# 11_FPGA_power.net
KiCad netlist of a schematic drawn in Altium Designer
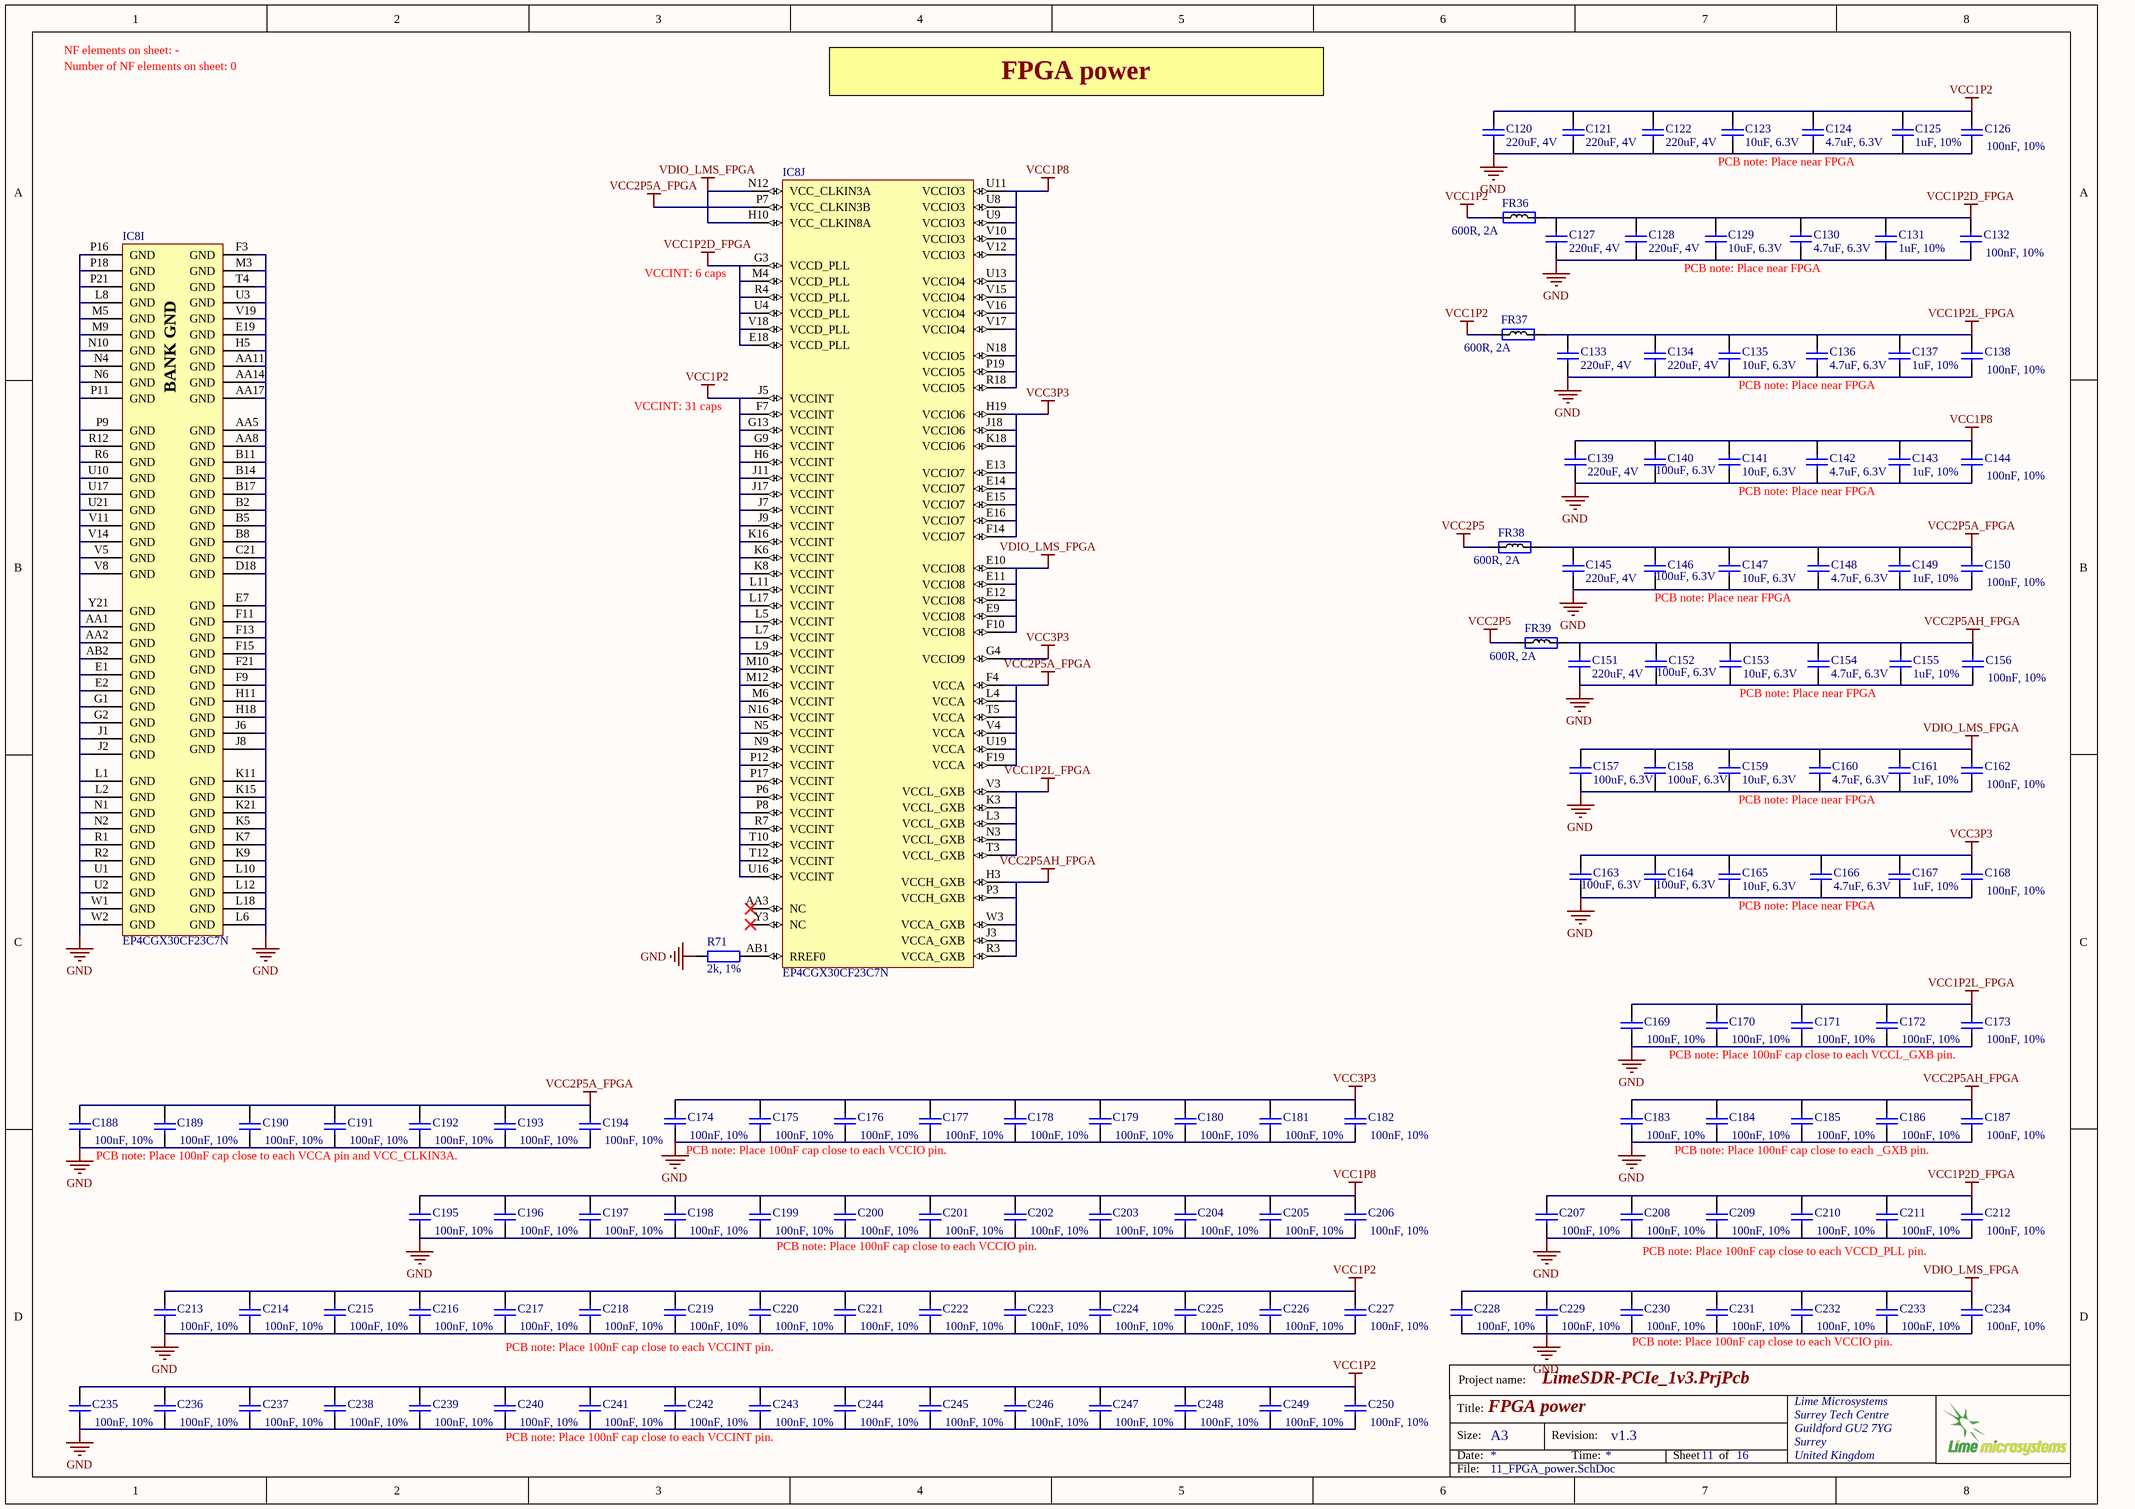
[diagram p0: 11_FPGA_power.SchDoc]

(export (version "E")
  (design (tool "Eeschema 10.0.6"))
  (components
    (comp (ref "C120")
      (value "220uF, 4V")
      (footprint "CAP1206")
      (fields
        (field (name "MANUFACTURER PART NUMBER") "GRM31CR60G227ME11L")
        (field (name "MANUFACTURER") "Murata Electronics North America")
        (field (name "TOLERANCE") "±20%")
      )
      (libsource (lib "LimeFPGAboard_schLib") (part "Cap_1206"))
    )
    (comp (ref "C121")
      (value "220uF, 4V")
      (footprint "CAP1206")
      (fields
        (field (name "MANUFACTURER PART NUMBER") "GRM31CR60G227ME11L")
        (field (name "MANUFACTURER") "Murata Electronics North America")
        (field (name "TOLERANCE") "±20%")
      )
      (libsource (lib "LimeFPGAboard_schLib") (part "Cap_1206"))
    )
    (comp (ref "C122")
      (value "220uF, 4V")
      (footprint "CAP1206")
      (fields
        (field (name "MANUFACTURER PART NUMBER") "GRM31CR60G227ME11L")
        (field (name "MANUFACTURER") "Murata Electronics North America")
        (field (name "TOLERANCE") "±20%")
      )
      (libsource (lib "LimeFPGAboard_schLib") (part "Cap_1206"))
    )
    (comp (ref "C123")
      (value "10uF, 6.3V")
      (footprint "CAP0603")
      (fields (field (name "TOLERANCE") "±20%") (field (name "MANUFACTURER") "Yageo"))
      (libsource (lib "LimeFPGAboard_schLib") (part "Cap_0603"))
    )
    (comp (ref "C124")
      (value "4.7uF, 6.3V")
      (footprint "CAP0402")
      (fields
        (field (name "MANUFACTURER") "Murata Electronics North America")
        (field (name "TOLERANCE") "±20%")
      )
      (libsource (lib "LimeMicroAltiumLib_schLib") (part "Cap_0402"))
    )
    (comp (ref "C125")
      (value "1uF, 10%")
      (footprint "CAP0402")
      (fields (field (name "MANUFACTURER") "TDK"))
      (libsource (lib "LimeMicroAltiumLib_schLib") (part "Cap_0402"))
    )
    (comp (ref "C126")
      (value "100nF, 10%")
      (footprint "CAP0402")
      (fields
        (field (name "TOLERANCE") "10 %")
        (field (name "MANUFACTURER") "Murata Electronics")
        (field (name "MANUFACTURER PART NUMBER") "GRM155R71C104KA88D")
      )
      (libsource (lib "LimeFPGAboard_schLib") (part "Cap_0603"))
    )
    (comp (ref "C127")
      (value "220uF, 4V")
      (footprint "CAP1206")
      (fields
        (field (name "MANUFACTURER PART NUMBER") "GRM31CR60G227ME11L")
        (field (name "MANUFACTURER") "Murata Electronics North America")
        (field (name "TOLERANCE") "±20%")
      )
      (libsource (lib "LimeFPGAboard_schLib") (part "Cap_1206"))
    )
    (comp (ref "C128")
      (value "220uF, 4V")
      (footprint "CAP1206")
      (fields
        (field (name "MANUFACTURER PART NUMBER") "GRM31CR60G227ME11L")
        (field (name "MANUFACTURER") "Murata Electronics North America")
        (field (name "TOLERANCE") "±20%")
      )
      (libsource (lib "LimeFPGAboard_schLib") (part "Cap_1206"))
    )
    (comp (ref "C129")
      (value "10uF, 6.3V")
      (footprint "CAP0603")
      (fields (field (name "TOLERANCE") "±20%") (field (name "MANUFACTURER") "Yageo"))
      (libsource (lib "LimeFPGAboard_schLib") (part "Cap_0603"))
    )
    (comp (ref "C130")
      (value "4.7uF, 6.3V")
      (footprint "CAP0402")
      (fields
        (field (name "MANUFACTURER") "Murata Electronics North America")
        (field (name "TOLERANCE") "±20%")
      )
      (libsource (lib "LimeMicroAltiumLib_schLib") (part "Cap_0402"))
    )
    (comp (ref "C131")
      (value "1uF, 10%")
      (footprint "CAP0402")
      (fields (field (name "MANUFACTURER") "TDK"))
      (libsource (lib "LimeMicroAltiumLib_schLib") (part "Cap_0402"))
    )
    (comp (ref "C132")
      (value "100nF, 10%")
      (footprint "CAP0402")
      (fields
        (field (name "TOLERANCE") "10 %")
        (field (name "MANUFACTURER") "Murata Electronics")
        (field (name "MANUFACTURER PART NUMBER") "GRM155R71C104KA88D")
      )
      (libsource (lib "LimeFPGAboard_schLib") (part "Cap_0603"))
    )
    (comp (ref "C133")
      (value "220uF, 4V")
      (footprint "CAP1206")
      (fields
        (field (name "MANUFACTURER PART NUMBER") "GRM31CR60G227ME11L")
        (field (name "MANUFACTURER") "Murata Electronics North America")
        (field (name "TOLERANCE") "±20%")
      )
      (libsource (lib "LimeFPGAboard_schLib") (part "Cap_1206"))
    )
    (comp (ref "C134")
      (value "220uF, 4V")
      (footprint "CAP1206")
      (fields
        (field (name "MANUFACTURER PART NUMBER") "GRM31CR60G227ME11L")
        (field (name "MANUFACTURER") "Murata Electronics North America")
        (field (name "TOLERANCE") "±20%")
      )
      (libsource (lib "LimeFPGAboard_schLib") (part "Cap_1206"))
    )
    (comp (ref "C135")
      (value "10uF, 6.3V")
      (footprint "CAP0603")
      (fields (field (name "TOLERANCE") "±20%") (field (name "MANUFACTURER") "Yageo"))
      (libsource (lib "LimeFPGAboard_schLib") (part "Cap_0603"))
    )
    (comp (ref "C136")
      (value "4.7uF, 6.3V")
      (footprint "CAP0402")
      (fields
        (field (name "MANUFACTURER") "Murata Electronics North America")
        (field (name "TOLERANCE") "±20%")
      )
      (libsource (lib "LimeMicroAltiumLib_schLib") (part "Cap_0402"))
    )
    (comp (ref "C137")
      (value "1uF, 10%")
      (footprint "CAP0402")
      (fields (field (name "MANUFACTURER") "TDK"))
      (libsource (lib "LimeMicroAltiumLib_schLib") (part "Cap_0402"))
    )
    (comp (ref "C138")
      (value "100nF, 10%")
      (footprint "CAP0402")
      (fields
        (field (name "TOLERANCE") "10 %")
        (field (name "MANUFACTURER") "Murata Electronics")
        (field (name "MANUFACTURER PART NUMBER") "GRM155R71C104KA88D")
      )
      (libsource (lib "LimeFPGAboard_schLib") (part "Cap_0603"))
    )
    (comp (ref "C139")
      (value "220uF, 4V")
      (footprint "CAP1206")
      (fields
        (field (name "MANUFACTURER PART NUMBER") "GRM31CR60G227ME11L")
        (field (name "MANUFACTURER") "Murata Electronics North America")
        (field (name "TOLERANCE") "±20%")
      )
      (libsource (lib "LimeFPGAboard_schLib") (part "Cap_1206"))
    )
    (comp (ref "C140")
      (value "100uF, 6.3V")
      (footprint "CAP1206")
      (fields (field (name "MANUFACTURER") "MURATA"))
      (libsource (lib "LimeFPGAboard_schLib") (part "Cap_1206"))
    )
    (comp (ref "C141")
      (value "10uF, 6.3V")
      (footprint "CAP0603")
      (fields (field (name "TOLERANCE") "±20%") (field (name "MANUFACTURER") "Yageo"))
      (libsource (lib "LimeFPGAboard_schLib") (part "Cap_0603"))
    )
    (comp (ref "C142")
      (value "4.7uF, 6.3V")
      (footprint "CAP0402")
      (fields
        (field (name "MANUFACTURER") "Murata Electronics North America")
        (field (name "TOLERANCE") "±20%")
      )
      (libsource (lib "LimeMicroAltiumLib_schLib") (part "Cap_0402"))
    )
    (comp (ref "C143")
      (value "1uF, 10%")
      (footprint "CAP0402")
      (fields (field (name "MANUFACTURER") "TDK"))
      (libsource (lib "LimeMicroAltiumLib_schLib") (part "Cap_0402"))
    )
    (comp (ref "C144")
      (value "100nF, 10%")
      (footprint "CAP0402")
      (fields
        (field (name "TOLERANCE") "10 %")
        (field (name "MANUFACTURER") "Murata Electronics")
        (field (name "MANUFACTURER PART NUMBER") "GRM155R71C104KA88D")
      )
      (libsource (lib "LimeFPGAboard_schLib") (part "Cap_0603"))
    )
    (comp (ref "C145")
      (value "220uF, 4V")
      (footprint "CAP1206")
      (fields
        (field (name "MANUFACTURER PART NUMBER") "GRM31CR60G227ME11L")
        (field (name "MANUFACTURER") "Murata Electronics North America")
        (field (name "TOLERANCE") "±20%")
      )
      (libsource (lib "LimeFPGAboard_schLib") (part "Cap_1206"))
    )
    (comp (ref "C146")
      (value "100uF, 6.3V")
      (footprint "CAP1206")
      (fields (field (name "MANUFACTURER") "MURATA"))
      (libsource (lib "LimeFPGAboard_schLib") (part "Cap_1206"))
    )
    (comp (ref "C147")
      (value "10uF, 6.3V")
      (footprint "CAP0603")
      (fields (field (name "TOLERANCE") "±20%") (field (name "MANUFACTURER") "Yageo"))
      (libsource (lib "LimeFPGAboard_schLib") (part "Cap_0603"))
    )
    (comp (ref "C148")
      (value "4.7uF, 6.3V")
      (footprint "CAP0402")
      (fields
        (field (name "MANUFACTURER") "Murata Electronics North America")
        (field (name "TOLERANCE") "±20%")
      )
      (libsource (lib "LimeMicroAltiumLib_schLib") (part "Cap_0402"))
    )
    (comp (ref "C149")
      (value "1uF, 10%")
      (footprint "CAP0402")
      (fields (field (name "MANUFACTURER") "TDK"))
      (libsource (lib "LimeMicroAltiumLib_schLib") (part "Cap_0402"))
    )
    (comp (ref "C150")
      (value "100nF, 10%")
      (footprint "CAP0402")
      (fields
        (field (name "TOLERANCE") "10 %")
        (field (name "MANUFACTURER") "Murata Electronics")
        (field (name "MANUFACTURER PART NUMBER") "GRM155R71C104KA88D")
      )
      (libsource (lib "LimeFPGAboard_schLib") (part "Cap_0603"))
    )
    (comp (ref "C151")
      (value "220uF, 4V")
      (footprint "CAP1206")
      (fields
        (field (name "MANUFACTURER PART NUMBER") "GRM31CR60G227ME11L")
        (field (name "MANUFACTURER") "Murata Electronics North America")
        (field (name "TOLERANCE") "±20%")
      )
      (libsource (lib "LimeFPGAboard_schLib") (part "Cap_1206"))
    )
    (comp (ref "C152")
      (value "100uF, 6.3V")
      (footprint "CAP1206")
      (fields (field (name "MANUFACTURER") "MURATA"))
      (libsource (lib "LimeFPGAboard_schLib") (part "Cap_1206"))
    )
    (comp (ref "C153")
      (value "10uF, 6.3V")
      (footprint "CAP0603")
      (fields (field (name "TOLERANCE") "±20%") (field (name "MANUFACTURER") "Yageo"))
      (libsource (lib "LimeFPGAboard_schLib") (part "Cap_0603"))
    )
    (comp (ref "C154")
      (value "4.7uF, 6.3V")
      (footprint "CAP0402")
      (fields
        (field (name "MANUFACTURER") "Murata Electronics North America")
        (field (name "TOLERANCE") "±20%")
      )
      (libsource (lib "LimeMicroAltiumLib_schLib") (part "Cap_0402"))
    )
    (comp (ref "C155")
      (value "1uF, 10%")
      (footprint "CAP0402")
      (fields (field (name "MANUFACTURER") "TDK"))
      (libsource (lib "LimeMicroAltiumLib_schLib") (part "Cap_0402"))
    )
    (comp (ref "C156")
      (value "100nF, 10%")
      (footprint "CAP0402")
      (fields
        (field (name "TOLERANCE") "10 %")
        (field (name "MANUFACTURER") "Murata Electronics")
        (field (name "MANUFACTURER PART NUMBER") "GRM155R71C104KA88D")
      )
      (libsource (lib "LimeFPGAboard_schLib") (part "Cap_0603"))
    )
    (comp (ref "C157")
      (value "100uF, 6.3V")
      (footprint "CAP1206")
      (fields (field (name "MANUFACTURER") "MURATA"))
      (libsource (lib "LimeFPGAboard_schLib") (part "Cap_1206"))
    )
    (comp (ref "C158")
      (value "100uF, 6.3V")
      (footprint "CAP1206")
      (fields (field (name "MANUFACTURER") "MURATA"))
      (libsource (lib "LimeFPGAboard_schLib") (part "Cap_1206"))
    )
    (comp (ref "C159")
      (value "10uF, 6.3V")
      (footprint "CAP0603")
      (fields (field (name "TOLERANCE") "±20%") (field (name "MANUFACTURER") "Yageo"))
      (libsource (lib "LimeFPGAboard_schLib") (part "Cap_0603"))
    )
    (comp (ref "C160")
      (value "4.7uF, 6.3V")
      (footprint "CAP0402")
      (fields
        (field (name "MANUFACTURER") "Murata Electronics North America")
        (field (name "TOLERANCE") "±20%")
      )
      (libsource (lib "LimeMicroAltiumLib_schLib") (part "Cap_0402"))
    )
    (comp (ref "C161")
      (value "1uF, 10%")
      (footprint "CAP0402")
      (fields (field (name "MANUFACTURER") "TDK"))
      (libsource (lib "LimeMicroAltiumLib_schLib") (part "Cap_0402"))
    )
    (comp (ref "C162")
      (value "100nF, 10%")
      (footprint "CAP0402")
      (fields
        (field (name "TOLERANCE") "10 %")
        (field (name "MANUFACTURER") "Murata Electronics")
        (field (name "MANUFACTURER PART NUMBER") "GRM155R71C104KA88D")
      )
      (libsource (lib "LimeFPGAboard_schLib") (part "Cap_0603"))
    )
    (comp (ref "C163")
      (value "100uF, 6.3V")
      (footprint "CAP1206")
      (fields (field (name "MANUFACTURER") "MURATA"))
      (libsource (lib "LimeFPGAboard_schLib") (part "Cap_1206"))
    )
    (comp (ref "C164")
      (value "100uF, 6.3V")
      (footprint "CAP1206")
      (fields (field (name "MANUFACTURER") "MURATA"))
      (libsource (lib "LimeFPGAboard_schLib") (part "Cap_1206"))
    )
    (comp (ref "C165")
      (value "10uF, 6.3V")
      (footprint "CAP0603")
      (fields (field (name "TOLERANCE") "±20%") (field (name "MANUFACTURER") "Yageo"))
      (libsource (lib "LimeFPGAboard_schLib") (part "Cap_0603"))
    )
    (comp (ref "C166")
      (value "4.7uF, 6.3V")
      (footprint "CAP0402")
      (fields
        (field (name "MANUFACTURER") "Murata Electronics North America")
        (field (name "TOLERANCE") "±20%")
      )
      (libsource (lib "LimeMicroAltiumLib_schLib") (part "Cap_0402"))
    )
    (comp (ref "C167")
      (value "1uF, 10%")
      (footprint "CAP0402")
      (fields (field (name "MANUFACTURER") "TDK"))
      (libsource (lib "LimeMicroAltiumLib_schLib") (part "Cap_0402"))
    )
    (comp (ref "C168")
      (value "100nF, 10%")
      (footprint "CAP0402")
      (fields
        (field (name "TOLERANCE") "10 %")
        (field (name "MANUFACTURER") "Murata Electronics")
        (field (name "MANUFACTURER PART NUMBER") "GRM155R71C104KA88D")
      )
      (libsource (lib "LimeFPGAboard_schLib") (part "Cap_0603"))
    )
    (comp (ref "C169")
      (value "100nF, 10%")
      (footprint "CAP0402")
      (fields
        (field (name "TOLERANCE") "10 %")
        (field (name "MANUFACTURER") "Murata Electronics")
        (field (name "MANUFACTURER PART NUMBER") "GRM155R71C104KA88D")
      )
      (libsource (lib "LimeFPGAboard_schLib") (part "Cap_0603"))
    )
    (comp (ref "C170")
      (value "100nF, 10%")
      (footprint "CAP0402")
      (fields
        (field (name "TOLERANCE") "10 %")
        (field (name "MANUFACTURER") "Murata Electronics")
        (field (name "MANUFACTURER PART NUMBER") "GRM155R71C104KA88D")
      )
      (libsource (lib "LimeFPGAboard_schLib") (part "Cap_0603"))
    )
    (comp (ref "C171")
      (value "100nF, 10%")
      (footprint "CAP0402")
      (fields
        (field (name "TOLERANCE") "10 %")
        (field (name "MANUFACTURER") "Murata Electronics")
        (field (name "MANUFACTURER PART NUMBER") "GRM155R71C104KA88D")
      )
      (libsource (lib "LimeFPGAboard_schLib") (part "Cap_0603"))
    )
    (comp (ref "C172")
      (value "100nF, 10%")
      (footprint "CAP0402")
      (fields
        (field (name "TOLERANCE") "10 %")
        (field (name "MANUFACTURER") "Murata Electronics")
        (field (name "MANUFACTURER PART NUMBER") "GRM155R71C104KA88D")
      )
      (libsource (lib "LimeFPGAboard_schLib") (part "Cap_0603"))
    )
    (comp (ref "C173")
      (value "100nF, 10%")
      (footprint "CAP0402")
      (fields
        (field (name "TOLERANCE") "10 %")
        (field (name "MANUFACTURER") "Murata Electronics")
        (field (name "MANUFACTURER PART NUMBER") "GRM155R71C104KA88D")
      )
      (libsource (lib "LimeFPGAboard_schLib") (part "Cap_0603"))
    )
    (comp (ref "C174")
      (value "100nF, 10%")
      (footprint "CAP0402")
      (fields
        (field (name "TOLERANCE") "10 %")
        (field (name "MANUFACTURER") "Murata Electronics")
        (field (name "MANUFACTURER PART NUMBER") "GRM155R71C104KA88D")
      )
      (libsource (lib "LimeFPGAboard_schLib") (part "Cap_0603"))
    )
    (comp (ref "C175")
      (value "100nF, 10%")
      (footprint "CAP0402")
      (fields
        (field (name "TOLERANCE") "10 %")
        (field (name "MANUFACTURER") "Murata Electronics")
        (field (name "MANUFACTURER PART NUMBER") "GRM155R71C104KA88D")
      )
      (libsource (lib "LimeFPGAboard_schLib") (part "Cap_0603"))
    )
    (comp (ref "C176")
      (value "100nF, 10%")
      (footprint "CAP0402")
      (fields
        (field (name "TOLERANCE") "10 %")
        (field (name "MANUFACTURER") "Murata Electronics")
        (field (name "MANUFACTURER PART NUMBER") "GRM155R71C104KA88D")
      )
      (libsource (lib "LimeFPGAboard_schLib") (part "Cap_0603"))
    )
    (comp (ref "C177")
      (value "100nF, 10%")
      (footprint "CAP0402")
      (fields
        (field (name "TOLERANCE") "10 %")
        (field (name "MANUFACTURER") "Murata Electronics")
        (field (name "MANUFACTURER PART NUMBER") "GRM155R71C104KA88D")
      )
      (libsource (lib "LimeFPGAboard_schLib") (part "Cap_0603"))
    )
    (comp (ref "C178")
      (value "100nF, 10%")
      (footprint "CAP0402")
      (fields
        (field (name "TOLERANCE") "10 %")
        (field (name "MANUFACTURER") "Murata Electronics")
        (field (name "MANUFACTURER PART NUMBER") "GRM155R71C104KA88D")
      )
      (libsource (lib "LimeFPGAboard_schLib") (part "Cap_0603"))
    )
    (comp (ref "C179")
      (value "100nF, 10%")
      (footprint "CAP0402")
      (fields
        (field (name "TOLERANCE") "10 %")
        (field (name "MANUFACTURER") "Murata Electronics")
        (field (name "MANUFACTURER PART NUMBER") "GRM155R71C104KA88D")
      )
      (libsource (lib "LimeFPGAboard_schLib") (part "Cap_0603"))
    )
    (comp (ref "C180")
      (value "100nF, 10%")
      (footprint "CAP0402")
      (fields
        (field (name "TOLERANCE") "10 %")
        (field (name "MANUFACTURER") "Murata Electronics")
        (field (name "MANUFACTURER PART NUMBER") "GRM155R71C104KA88D")
      )
      (libsource (lib "LimeFPGAboard_schLib") (part "Cap_0603"))
    )
    (comp (ref "C181")
      (value "100nF, 10%")
      (footprint "CAP0402")
      (fields
        (field (name "TOLERANCE") "10 %")
        (field (name "MANUFACTURER") "Murata Electronics")
        (field (name "MANUFACTURER PART NUMBER") "GRM155R71C104KA88D")
      )
      (libsource (lib "LimeFPGAboard_schLib") (part "Cap_0603"))
    )
    (comp (ref "C182")
      (value "100nF, 10%")
      (footprint "CAP0402")
      (fields
        (field (name "TOLERANCE") "10 %")
        (field (name "MANUFACTURER") "Murata Electronics")
        (field (name "MANUFACTURER PART NUMBER") "GRM155R71C104KA88D")
      )
      (libsource (lib "LimeFPGAboard_schLib") (part "Cap_0603"))
    )
    (comp (ref "C183")
      (value "100nF, 10%")
      (footprint "CAP0402")
      (fields
        (field (name "TOLERANCE") "10 %")
        (field (name "MANUFACTURER") "Murata Electronics")
        (field (name "MANUFACTURER PART NUMBER") "GRM155R71C104KA88D")
      )
      (libsource (lib "LimeFPGAboard_schLib") (part "Cap_0603"))
    )
    (comp (ref "C184")
      (value "100nF, 10%")
      (footprint "CAP0402")
      (fields
        (field (name "TOLERANCE") "10 %")
        (field (name "MANUFACTURER") "Murata Electronics")
        (field (name "MANUFACTURER PART NUMBER") "GRM155R71C104KA88D")
      )
      (libsource (lib "LimeFPGAboard_schLib") (part "Cap_0603"))
    )
    (comp (ref "C185")
      (value "100nF, 10%")
      (footprint "CAP0402")
      (fields
        (field (name "TOLERANCE") "10 %")
        (field (name "MANUFACTURER") "Murata Electronics")
        (field (name "MANUFACTURER PART NUMBER") "GRM155R71C104KA88D")
      )
      (libsource (lib "LimeFPGAboard_schLib") (part "Cap_0603"))
    )
    (comp (ref "C186")
      (value "100nF, 10%")
      (footprint "CAP0402")
      (fields
        (field (name "TOLERANCE") "10 %")
        (field (name "MANUFACTURER") "Murata Electronics")
        (field (name "MANUFACTURER PART NUMBER") "GRM155R71C104KA88D")
      )
      (libsource (lib "LimeFPGAboard_schLib") (part "Cap_0603"))
    )
    (comp (ref "C187")
      (value "100nF, 10%")
      (footprint "CAP0402")
      (fields
        (field (name "TOLERANCE") "10 %")
        (field (name "MANUFACTURER") "Murata Electronics")
        (field (name "MANUFACTURER PART NUMBER") "GRM155R71C104KA88D")
      )
      (libsource (lib "LimeFPGAboard_schLib") (part "Cap_0603"))
    )
    (comp (ref "C188")
      (value "100nF, 10%")
      (footprint "CAP0402")
      (fields
        (field (name "TOLERANCE") "10 %")
        (field (name "MANUFACTURER") "Murata Electronics")
        (field (name "MANUFACTURER PART NUMBER") "GRM155R71C104KA88D")
      )
      (libsource (lib "LimeFPGAboard_schLib") (part "Cap_0603"))
    )
    (comp (ref "C189")
      (value "100nF, 10%")
      (footprint "CAP0402")
      (fields
        (field (name "TOLERANCE") "10 %")
        (field (name "MANUFACTURER") "Murata Electronics")
        (field (name "MANUFACTURER PART NUMBER") "GRM155R71C104KA88D")
      )
      (libsource (lib "LimeFPGAboard_schLib") (part "Cap_0603"))
    )
    (comp (ref "C190")
      (value "100nF, 10%")
      (footprint "CAP0402")
      (fields
        (field (name "TOLERANCE") "10 %")
        (field (name "MANUFACTURER") "Murata Electronics")
        (field (name "MANUFACTURER PART NUMBER") "GRM155R71C104KA88D")
      )
      (libsource (lib "LimeFPGAboard_schLib") (part "Cap_0603"))
    )
    (comp (ref "C191")
      (value "100nF, 10%")
      (footprint "CAP0402")
      (fields
        (field (name "TOLERANCE") "10 %")
        (field (name "MANUFACTURER") "Murata Electronics")
        (field (name "MANUFACTURER PART NUMBER") "GRM155R71C104KA88D")
      )
      (libsource (lib "LimeFPGAboard_schLib") (part "Cap_0603"))
    )
    (comp (ref "C192")
      (value "100nF, 10%")
      (footprint "CAP0402")
      (fields
        (field (name "TOLERANCE") "10 %")
        (field (name "MANUFACTURER") "Murata Electronics")
        (field (name "MANUFACTURER PART NUMBER") "GRM155R71C104KA88D")
      )
      (libsource (lib "LimeFPGAboard_schLib") (part "Cap_0603"))
    )
    (comp (ref "C193")
      (value "100nF, 10%")
      (footprint "CAP0402")
      (fields
        (field (name "TOLERANCE") "10 %")
        (field (name "MANUFACTURER") "Murata Electronics")
        (field (name "MANUFACTURER PART NUMBER") "GRM155R71C104KA88D")
      )
      (libsource (lib "LimeFPGAboard_schLib") (part "Cap_0603"))
    )
    (comp (ref "C194")
      (value "100nF, 10%")
      (footprint "CAP0402")
      (fields
        (field (name "TOLERANCE") "10 %")
        (field (name "MANUFACTURER") "Murata Electronics")
        (field (name "MANUFACTURER PART NUMBER") "GRM155R71C104KA88D")
      )
      (libsource (lib "LimeFPGAboard_schLib") (part "Cap_0603"))
    )
    (comp (ref "C195")
      (value "100nF, 10%")
      (footprint "CAP0402")
      (fields
        (field (name "TOLERANCE") "10 %")
        (field (name "MANUFACTURER") "Murata Electronics")
        (field (name "MANUFACTURER PART NUMBER") "GRM155R71C104KA88D")
      )
      (libsource (lib "LimeFPGAboard_schLib") (part "Cap_0603"))
    )
    (comp (ref "C196")
      (value "100nF, 10%")
      (footprint "CAP0402")
      (fields
        (field (name "TOLERANCE") "10 %")
        (field (name "MANUFACTURER") "Murata Electronics")
        (field (name "MANUFACTURER PART NUMBER") "GRM155R71C104KA88D")
      )
      (libsource (lib "LimeFPGAboard_schLib") (part "Cap_0603"))
    )
    (comp (ref "C197")
      (value "100nF, 10%")
      (footprint "CAP0402")
      (fields
        (field (name "TOLERANCE") "10 %")
        (field (name "MANUFACTURER") "Murata Electronics")
        (field (name "MANUFACTURER PART NUMBER") "GRM155R71C104KA88D")
      )
      (libsource (lib "LimeFPGAboard_schLib") (part "Cap_0603"))
    )
    (comp (ref "C198")
      (value "100nF, 10%")
      (footprint "CAP0402")
      (fields
        (field (name "TOLERANCE") "10 %")
        (field (name "MANUFACTURER") "Murata Electronics")
        (field (name "MANUFACTURER PART NUMBER") "GRM155R71C104KA88D")
      )
      (libsource (lib "LimeFPGAboard_schLib") (part "Cap_0603"))
    )
    (comp (ref "C199")
      (value "100nF, 10%")
      (footprint "CAP0402")
      (fields
        (field (name "TOLERANCE") "10 %")
        (field (name "MANUFACTURER") "Murata Electronics")
        (field (name "MANUFACTURER PART NUMBER") "GRM155R71C104KA88D")
      )
      (libsource (lib "LimeFPGAboard_schLib") (part "Cap_0603"))
    )
    (comp (ref "C200")
      (value "100nF, 10%")
      (footprint "CAP0402")
      (fields
        (field (name "TOLERANCE") "10 %")
        (field (name "MANUFACTURER") "Murata Electronics")
        (field (name "MANUFACTURER PART NUMBER") "GRM155R71C104KA88D")
      )
      (libsource (lib "LimeFPGAboard_schLib") (part "Cap_0603"))
    )
    (comp (ref "C201")
      (value "100nF, 10%")
      (footprint "CAP0402")
      (fields
        (field (name "TOLERANCE") "10 %")
        (field (name "MANUFACTURER") "Murata Electronics")
        (field (name "MANUFACTURER PART NUMBER") "GRM155R71C104KA88D")
      )
      (libsource (lib "LimeFPGAboard_schLib") (part "Cap_0603"))
    )
    (comp (ref "C202")
      (value "100nF, 10%")
      (footprint "CAP0402")
      (fields
        (field (name "TOLERANCE") "10 %")
        (field (name "MANUFACTURER") "Murata Electronics")
        (field (name "MANUFACTURER PART NUMBER") "GRM155R71C104KA88D")
      )
      (libsource (lib "LimeFPGAboard_schLib") (part "Cap_0603"))
    )
    (comp (ref "C203")
      (value "100nF, 10%")
      (footprint "CAP0402")
      (fields
        (field (name "TOLERANCE") "10 %")
        (field (name "MANUFACTURER") "Murata Electronics")
        (field (name "MANUFACTURER PART NUMBER") "GRM155R71C104KA88D")
      )
      (libsource (lib "LimeFPGAboard_schLib") (part "Cap_0603"))
    )
    (comp (ref "C204")
      (value "100nF, 10%")
      (footprint "CAP0402")
      (fields
        (field (name "TOLERANCE") "10 %")
        (field (name "MANUFACTURER") "Murata Electronics")
        (field (name "MANUFACTURER PART NUMBER") "GRM155R71C104KA88D")
      )
      (libsource (lib "LimeFPGAboard_schLib") (part "Cap_0603"))
    )
    (comp (ref "C205")
      (value "100nF, 10%")
      (footprint "CAP0402")
      (fields
        (field (name "TOLERANCE") "10 %")
        (field (name "MANUFACTURER") "Murata Electronics")
        (field (name "MANUFACTURER PART NUMBER") "GRM155R71C104KA88D")
      )
      (libsource (lib "LimeFPGAboard_schLib") (part "Cap_0603"))
    )
    (comp (ref "C206")
      (value "100nF, 10%")
      (footprint "CAP0402")
      (fields
        (field (name "TOLERANCE") "10 %")
        (field (name "MANUFACTURER") "Murata Electronics")
        (field (name "MANUFACTURER PART NUMBER") "GRM155R71C104KA88D")
      )
      (libsource (lib "LimeFPGAboard_schLib") (part "Cap_0603"))
    )
    (comp (ref "C207")
      (value "100nF, 10%")
      (footprint "CAP0402")
      (fields
        (field (name "TOLERANCE") "10 %")
        (field (name "MANUFACTURER") "Murata Electronics")
        (field (name "MANUFACTURER PART NUMBER") "GRM155R71C104KA88D")
      )
      (libsource (lib "LimeFPGAboard_schLib") (part "Cap_0603"))
    )
    (comp (ref "C208")
      (value "100nF, 10%")
      (footprint "CAP0402")
      (fields
        (field (name "TOLERANCE") "10 %")
        (field (name "MANUFACTURER") "Murata Electronics")
        (field (name "MANUFACTURER PART NUMBER") "GRM155R71C104KA88D")
      )
      (libsource (lib "LimeFPGAboard_schLib") (part "Cap_0603"))
    )
    (comp (ref "C209")
      (value "100nF, 10%")
      (footprint "CAP0402")
      (fields
        (field (name "TOLERANCE") "10 %")
        (field (name "MANUFACTURER") "Murata Electronics")
        (field (name "MANUFACTURER PART NUMBER") "GRM155R71C104KA88D")
      )
      (libsource (lib "LimeFPGAboard_schLib") (part "Cap_0603"))
    )
    (comp (ref "C210")
      (value "100nF, 10%")
      (footprint "CAP0402")
      (fields
        (field (name "TOLERANCE") "10 %")
        (field (name "MANUFACTURER") "Murata Electronics")
        (field (name "MANUFACTURER PART NUMBER") "GRM155R71C104KA88D")
      )
      (libsource (lib "LimeFPGAboard_schLib") (part "Cap_0603"))
    )
    (comp (ref "C211")
      (value "100nF, 10%")
      (footprint "CAP0402")
      (fields
        (field (name "TOLERANCE") "10 %")
        (field (name "MANUFACTURER") "Murata Electronics")
        (field (name "MANUFACTURER PART NUMBER") "GRM155R71C104KA88D")
      )
      (libsource (lib "LimeFPGAboard_schLib") (part "Cap_0603"))
    )
    (comp (ref "C212")
      (value "100nF, 10%")
      (footprint "CAP0402")
      (fields
        (field (name "TOLERANCE") "10 %")
        (field (name "MANUFACTURER") "Murata Electronics")
        (field (name "MANUFACTURER PART NUMBER") "GRM155R71C104KA88D")
      )
      (libsource (lib "LimeFPGAboard_schLib") (part "Cap_0603"))
    )
    (comp (ref "C213")
      (value "100nF, 10%")
      (footprint "CAP0402")
      (fields
        (field (name "TOLERANCE") "10 %")
        (field (name "MANUFACTURER") "Murata Electronics")
        (field (name "MANUFACTURER PART NUMBER") "GRM155R71C104KA88D")
      )
      (libsource (lib "LimeFPGAboard_schLib") (part "Cap_0603"))
    )
    (comp (ref "C214")
      (value "100nF, 10%")
      (footprint "CAP0402")
      (fields
        (field (name "TOLERANCE") "10 %")
        (field (name "MANUFACTURER") "Murata Electronics")
        (field (name "MANUFACTURER PART NUMBER") "GRM155R71C104KA88D")
      )
      (libsource (lib "LimeFPGAboard_schLib") (part "Cap_0603"))
    )
    (comp (ref "C215")
      (value "100nF, 10%")
      (footprint "CAP0402")
      (fields
        (field (name "TOLERANCE") "10 %")
        (field (name "MANUFACTURER") "Murata Electronics")
        (field (name "MANUFACTURER PART NUMBER") "GRM155R71C104KA88D")
      )
      (libsource (lib "LimeFPGAboard_schLib") (part "Cap_0603"))
    )
    (comp (ref "C216")
      (value "100nF, 10%")
      (footprint "CAP0402")
      (fields
        (field (name "TOLERANCE") "10 %")
        (field (name "MANUFACTURER") "Murata Electronics")
        (field (name "MANUFACTURER PART NUMBER") "GRM155R71C104KA88D")
      )
      (libsource (lib "LimeFPGAboard_schLib") (part "Cap_0603"))
    )
    (comp (ref "C217")
      (value "100nF, 10%")
      (footprint "CAP0402")
      (fields
        (field (name "TOLERANCE") "10 %")
        (field (name "MANUFACTURER") "Murata Electronics")
        (field (name "MANUFACTURER PART NUMBER") "GRM155R71C104KA88D")
      )
      (libsource (lib "LimeFPGAboard_schLib") (part "Cap_0603"))
    )
    (comp (ref "C218")
      (value "100nF, 10%")
      (footprint "CAP0402")
      (fields
        (field (name "TOLERANCE") "10 %")
        (field (name "MANUFACTURER") "Murata Electronics")
        (field (name "MANUFACTURER PART NUMBER") "GRM155R71C104KA88D")
      )
      (libsource (lib "LimeFPGAboard_schLib") (part "Cap_0603"))
    )
    (comp (ref "C219")
      (value "100nF, 10%")
      (footprint "CAP0402")
      (fields
        (field (name "TOLERANCE") "10 %")
        (field (name "MANUFACTURER") "Murata Electronics")
        (field (name "MANUFACTURER PART NUMBER") "GRM155R71C104KA88D")
      )
      (libsource (lib "LimeFPGAboard_schLib") (part "Cap_0603"))
    )
    (comp (ref "C220")
      (value "100nF, 10%")
      (footprint "CAP0402")
      (fields
        (field (name "TOLERANCE") "10 %")
        (field (name "MANUFACTURER") "Murata Electronics")
        (field (name "MANUFACTURER PART NUMBER") "GRM155R71C104KA88D")
      )
      (libsource (lib "LimeFPGAboard_schLib") (part "Cap_0603"))
    )
    (comp (ref "C221")
      (value "100nF, 10%")
      (footprint "CAP0402")
      (fields
        (field (name "TOLERANCE") "10 %")
        (field (name "MANUFACTURER") "Murata Electronics")
        (field (name "MANUFACTURER PART NUMBER") "GRM155R71C104KA88D")
      )
      (libsource (lib "LimeFPGAboard_schLib") (part "Cap_0603"))
    )
    (comp (ref "C222")
      (value "100nF, 10%")
      (footprint "CAP0402")
      (fields
        (field (name "TOLERANCE") "10 %")
        (field (name "MANUFACTURER") "Murata Electronics")
        (field (name "MANUFACTURER PART NUMBER") "GRM155R71C104KA88D")
      )
      (libsource (lib "LimeFPGAboard_schLib") (part "Cap_0603"))
    )
    (comp (ref "C223")
      (value "100nF, 10%")
      (footprint "CAP0402")
      (fields
        (field (name "TOLERANCE") "10 %")
        (field (name "MANUFACTURER") "Murata Electronics")
        (field (name "MANUFACTURER PART NUMBER") "GRM155R71C104KA88D")
      )
      (libsource (lib "LimeFPGAboard_schLib") (part "Cap_0603"))
    )
    (comp (ref "C224")
      (value "100nF, 10%")
      (footprint "CAP0402")
      (fields
        (field (name "TOLERANCE") "10 %")
        (field (name "MANUFACTURER") "Murata Electronics")
        (field (name "MANUFACTURER PART NUMBER") "GRM155R71C104KA88D")
      )
      (libsource (lib "LimeFPGAboard_schLib") (part "Cap_0603"))
    )
    (comp (ref "C225")
      (value "100nF, 10%")
      (footprint "CAP0402")
      (fields
        (field (name "TOLERANCE") "10 %")
        (field (name "MANUFACTURER") "Murata Electronics")
        (field (name "MANUFACTURER PART NUMBER") "GRM155R71C104KA88D")
      )
      (libsource (lib "LimeFPGAboard_schLib") (part "Cap_0603"))
    )
    (comp (ref "C226")
      (value "100nF, 10%")
      (footprint "CAP0402")
      (fields
        (field (name "TOLERANCE") "10 %")
        (field (name "MANUFACTURER") "Murata Electronics")
        (field (name "MANUFACTURER PART NUMBER") "GRM155R71C104KA88D")
      )
      (libsource (lib "LimeFPGAboard_schLib") (part "Cap_0603"))
    )
    (comp (ref "C227")
      (value "100nF, 10%")
      (footprint "CAP0402")
      (fields
        (field (name "TOLERANCE") "10 %")
        (field (name "MANUFACTURER") "Murata Electronics")
        (field (name "MANUFACTURER PART NUMBER") "GRM155R71C104KA88D")
      )
      (libsource (lib "LimeFPGAboard_schLib") (part "Cap_0603"))
    )
    (comp (ref "C228")
      (value "100nF, 10%")
      (footprint "CAP0402")
      (fields
        (field (name "TOLERANCE") "10 %")
        (field (name "MANUFACTURER") "Murata Electronics")
        (field (name "MANUFACTURER PART NUMBER") "GRM155R71C104KA88D")
      )
      (libsource (lib "LimeFPGAboard_schLib") (part "Cap_0603"))
    )
    (comp (ref "C229")
      (value "100nF, 10%")
      (footprint "CAP0402")
      (fields
        (field (name "TOLERANCE") "10 %")
        (field (name "MANUFACTURER") "Murata Electronics")
        (field (name "MANUFACTURER PART NUMBER") "GRM155R71C104KA88D")
      )
      (libsource (lib "LimeFPGAboard_schLib") (part "Cap_0603"))
    )
    (comp (ref "C230")
      (value "100nF, 10%")
      (footprint "CAP0402")
      (fields
        (field (name "TOLERANCE") "10 %")
        (field (name "MANUFACTURER") "Murata Electronics")
        (field (name "MANUFACTURER PART NUMBER") "GRM155R71C104KA88D")
      )
      (libsource (lib "LimeFPGAboard_schLib") (part "Cap_0603"))
    )
    (comp (ref "C231")
      (value "100nF, 10%")
      (footprint "CAP0402")
      (fields
        (field (name "TOLERANCE") "10 %")
        (field (name "MANUFACTURER") "Murata Electronics")
        (field (name "MANUFACTURER PART NUMBER") "GRM155R71C104KA88D")
      )
      (libsource (lib "LimeFPGAboard_schLib") (part "Cap_0603"))
    )
    (comp (ref "C232")
      (value "100nF, 10%")
      (footprint "CAP0402")
      (fields
        (field (name "TOLERANCE") "10 %")
        (field (name "MANUFACTURER") "Murata Electronics")
        (field (name "MANUFACTURER PART NUMBER") "GRM155R71C104KA88D")
      )
      (libsource (lib "LimeFPGAboard_schLib") (part "Cap_0603"))
    )
    (comp (ref "C233")
      (value "100nF, 10%")
      (footprint "CAP0402")
      (fields
        (field (name "TOLERANCE") "10 %")
        (field (name "MANUFACTURER") "Murata Electronics")
        (field (name "MANUFACTURER PART NUMBER") "GRM155R71C104KA88D")
      )
      (libsource (lib "LimeFPGAboard_schLib") (part "Cap_0603"))
    )
    (comp (ref "C234")
      (value "100nF, 10%")
      (footprint "CAP0402")
      (fields
        (field (name "TOLERANCE") "10 %")
        (field (name "MANUFACTURER") "Murata Electronics")
        (field (name "MANUFACTURER PART NUMBER") "GRM155R71C104KA88D")
      )
      (libsource (lib "LimeFPGAboard_schLib") (part "Cap_0603"))
    )
    (comp (ref "C235")
      (value "100nF, 10%")
      (footprint "CAP0402")
      (fields
        (field (name "TOLERANCE") "10 %")
        (field (name "MANUFACTURER") "Murata Electronics")
        (field (name "MANUFACTURER PART NUMBER") "GRM155R71C104KA88D")
      )
      (libsource (lib "LimeFPGAboard_schLib") (part "Cap_0603"))
    )
    (comp (ref "C236")
      (value "100nF, 10%")
      (footprint "CAP0402")
      (fields
        (field (name "TOLERANCE") "10 %")
        (field (name "MANUFACTURER") "Murata Electronics")
        (field (name "MANUFACTURER PART NUMBER") "GRM155R71C104KA88D")
      )
      (libsource (lib "LimeFPGAboard_schLib") (part "Cap_0603"))
    )
    (comp (ref "C237")
      (value "100nF, 10%")
      (footprint "CAP0402")
      (fields
        (field (name "TOLERANCE") "10 %")
        (field (name "MANUFACTURER") "Murata Electronics")
        (field (name "MANUFACTURER PART NUMBER") "GRM155R71C104KA88D")
      )
      (libsource (lib "LimeFPGAboard_schLib") (part "Cap_0603"))
    )
    (comp (ref "C238")
      (value "100nF, 10%")
      (footprint "CAP0402")
      (fields
        (field (name "TOLERANCE") "10 %")
        (field (name "MANUFACTURER") "Murata Electronics")
        (field (name "MANUFACTURER PART NUMBER") "GRM155R71C104KA88D")
      )
      (libsource (lib "LimeFPGAboard_schLib") (part "Cap_0603"))
    )
    (comp (ref "C239")
      (value "100nF, 10%")
      (footprint "CAP0402")
      (fields
        (field (name "TOLERANCE") "10 %")
        (field (name "MANUFACTURER") "Murata Electronics")
        (field (name "MANUFACTURER PART NUMBER") "GRM155R71C104KA88D")
      )
      (libsource (lib "LimeFPGAboard_schLib") (part "Cap_0603"))
    )
    (comp (ref "C240")
      (value "100nF, 10%")
      (footprint "CAP0402")
      (fields
        (field (name "TOLERANCE") "10 %")
        (field (name "MANUFACTURER") "Murata Electronics")
        (field (name "MANUFACTURER PART NUMBER") "GRM155R71C104KA88D")
      )
      (libsource (lib "LimeFPGAboard_schLib") (part "Cap_0603"))
    )
    (comp (ref "C241")
      (value "100nF, 10%")
      (footprint "CAP0402")
      (fields
        (field (name "TOLERANCE") "10 %")
        (field (name "MANUFACTURER") "Murata Electronics")
        (field (name "MANUFACTURER PART NUMBER") "GRM155R71C104KA88D")
      )
      (libsource (lib "LimeFPGAboard_schLib") (part "Cap_0603"))
    )
    (comp (ref "C242")
      (value "100nF, 10%")
      (footprint "CAP0402")
      (fields
        (field (name "TOLERANCE") "10 %")
        (field (name "MANUFACTURER") "Murata Electronics")
        (field (name "MANUFACTURER PART NUMBER") "GRM155R71C104KA88D")
      )
      (libsource (lib "LimeFPGAboard_schLib") (part "Cap_0603"))
    )
    (comp (ref "C243")
      (value "100nF, 10%")
      (footprint "CAP0402")
      (fields
        (field (name "TOLERANCE") "10 %")
        (field (name "MANUFACTURER") "Murata Electronics")
        (field (name "MANUFACTURER PART NUMBER") "GRM155R71C104KA88D")
      )
      (libsource (lib "LimeFPGAboard_schLib") (part "Cap_0603"))
    )
    (comp (ref "C244")
      (value "100nF, 10%")
      (footprint "CAP0402")
      (fields
        (field (name "TOLERANCE") "10 %")
        (field (name "MANUFACTURER") "Murata Electronics")
        (field (name "MANUFACTURER PART NUMBER") "GRM155R71C104KA88D")
      )
      (libsource (lib "LimeFPGAboard_schLib") (part "Cap_0603"))
    )
    (comp (ref "C245")
      (value "100nF, 10%")
      (footprint "CAP0402")
      (fields
        (field (name "TOLERANCE") "10 %")
        (field (name "MANUFACTURER") "Murata Electronics")
        (field (name "MANUFACTURER PART NUMBER") "GRM155R71C104KA88D")
      )
      (libsource (lib "LimeFPGAboard_schLib") (part "Cap_0603"))
    )
    (comp (ref "C246")
      (value "100nF, 10%")
      (footprint "CAP0402")
      (fields
        (field (name "TOLERANCE") "10 %")
        (field (name "MANUFACTURER") "Murata Electronics")
        (field (name "MANUFACTURER PART NUMBER") "GRM155R71C104KA88D")
      )
      (libsource (lib "LimeFPGAboard_schLib") (part "Cap_0603"))
    )
    (comp (ref "C247")
      (value "100nF, 10%")
      (footprint "CAP0402")
      (fields
        (field (name "TOLERANCE") "10 %")
        (field (name "MANUFACTURER") "Murata Electronics")
        (field (name "MANUFACTURER PART NUMBER") "GRM155R71C104KA88D")
      )
      (libsource (lib "LimeFPGAboard_schLib") (part "Cap_0603"))
    )
    (comp (ref "C248")
      (value "100nF, 10%")
      (footprint "CAP0402")
      (fields
        (field (name "TOLERANCE") "10 %")
        (field (name "MANUFACTURER") "Murata Electronics")
        (field (name "MANUFACTURER PART NUMBER") "GRM155R71C104KA88D")
      )
      (libsource (lib "LimeFPGAboard_schLib") (part "Cap_0603"))
    )
    (comp (ref "C249")
      (value "100nF, 10%")
      (footprint "CAP0402")
      (fields
        (field (name "TOLERANCE") "10 %")
        (field (name "MANUFACTURER") "Murata Electronics")
        (field (name "MANUFACTURER PART NUMBER") "GRM155R71C104KA88D")
      )
      (libsource (lib "LimeFPGAboard_schLib") (part "Cap_0603"))
    )
    (comp (ref "C250")
      (value "100nF, 10%")
      (footprint "CAP0402")
      (fields
        (field (name "TOLERANCE") "10 %")
        (field (name "MANUFACTURER") "Murata Electronics")
        (field (name "MANUFACTURER PART NUMBER") "GRM155R71C104KA88D")
      )
      (libsource (lib "LimeFPGAboard_schLib") (part "Cap_0603"))
    )
    (comp (ref "FR36")
      (value "600R, 2A")
      (footprint "RES0805")
      (fields (field (name "MANUFACTURER") "TDK Corporation"))
      (libsource (lib "LimeMicroAltiumLib_schLib") (part "Ferrite"))
    )
    (comp (ref "FR37")
      (value "600R, 2A")
      (footprint "RES0805")
      (fields (field (name "MANUFACTURER") "TDK Corporation"))
      (libsource (lib "LimeMicroAltiumLib_schLib") (part "Ferrite"))
    )
    (comp (ref "FR38")
      (value "600R, 2A")
      (footprint "RES0805")
      (fields (field (name "MANUFACTURER") "TDK Corporation"))
      (libsource (lib "LimeMicroAltiumLib_schLib") (part "Ferrite"))
    )
    (comp (ref "FR39")
      (value "600R, 2A")
      (footprint "RES0805")
      (fields (field (name "MANUFACTURER") "TDK Corporation"))
      (libsource (lib "LimeMicroAltiumLib_schLib") (part "Ferrite"))
    )
    (comp (ref "IC8")
      (value "EP4CGX30CF23C7N")
      (footprint "ALTR-FBGA484_A-200")
      (fields (field (name "MANUFACTURER") "Altera"))
      (libsource (lib "LimeMicroAltiumLib_schLib") (part "EP4CGX30CF23C7N"))
    )
    (comp (ref "R71")
      (value "2k, 1%")
      (footprint "RES0402")
      (fields
        (field (name "MANUFACTURER") "Yageo")
        (field (name "TOLERANCE") "±1%")
        (field (name "MANUFACTURER PART NUMBER") "RC0402FR-072KL")
      )
      (libsource (lib "LimeMicroAltiumLib_schLib") (part "Res_0402"))
    )
  )
  (nets
    (net (code "1") (name "GND") (class "Default")
      (node (ref "C120") (pin "1") (pinfunction "1_1") (pintype "passive"))
      (node (ref "C121") (pin "1") (pinfunction "1_1") (pintype "passive"))
      (node (ref "C122") (pin "1") (pinfunction "1_1") (pintype "passive"))
      (node (ref "C123") (pin "1") (pinfunction "1_1") (pintype "passive"))
      (node (ref "C124") (pin "1") (pinfunction "1_1") (pintype "passive"))
      (node (ref "C125") (pin "2") (pinfunction "2_2") (pintype "passive"))
      (node (ref "C126") (pin "2") (pinfunction "2_2") (pintype "passive"))
      (node (ref "C127") (pin "1") (pinfunction "1_1") (pintype "passive"))
      (node (ref "C128") (pin "1") (pinfunction "1_1") (pintype "passive"))
      (node (ref "C129") (pin "1") (pinfunction "1_1") (pintype "passive"))
      (node (ref "C130") (pin "1") (pinfunction "1_1") (pintype "passive"))
      (node (ref "C131") (pin "2") (pinfunction "2_2") (pintype "passive"))
      (node (ref "C132") (pin "2") (pinfunction "2_2") (pintype "passive"))
      (node (ref "C133") (pin "1") (pinfunction "1_1") (pintype "passive"))
      (node (ref "C134") (pin "1") (pinfunction "1_1") (pintype "passive"))
      (node (ref "C135") (pin "1") (pinfunction "1_1") (pintype "passive"))
      (node (ref "C136") (pin "1") (pinfunction "1_1") (pintype "passive"))
      (node (ref "C137") (pin "1") (pinfunction "1_1") (pintype "passive"))
      (node (ref "C138") (pin "2") (pinfunction "2_2") (pintype "passive"))
      (node (ref "C139") (pin "1") (pinfunction "1_1") (pintype "passive"))
      (node (ref "C140") (pin "1") (pinfunction "1_1") (pintype "passive"))
      (node (ref "C141") (pin "1") (pinfunction "1_1") (pintype "passive"))
      (node (ref "C142") (pin "1") (pinfunction "1_1") (pintype "passive"))
      (node (ref "C143") (pin "1") (pinfunction "1_1") (pintype "passive"))
      (node (ref "C144") (pin "2") (pinfunction "2_2") (pintype "passive"))
      (node (ref "C145") (pin "1") (pinfunction "1_1") (pintype "passive"))
      (node (ref "C146") (pin "1") (pinfunction "1_1") (pintype "passive"))
      (node (ref "C147") (pin "1") (pinfunction "1_1") (pintype "passive"))
      (node (ref "C148") (pin "1") (pinfunction "1_1") (pintype "passive"))
      (node (ref "C149") (pin "1") (pinfunction "1_1") (pintype "passive"))
      (node (ref "C150") (pin "2") (pinfunction "2_2") (pintype "passive"))
      (node (ref "C151") (pin "1") (pinfunction "1_1") (pintype "passive"))
      (node (ref "C152") (pin "1") (pinfunction "1_1") (pintype "passive"))
      (node (ref "C153") (pin "1") (pinfunction "1_1") (pintype "passive"))
      (node (ref "C154") (pin "1") (pinfunction "1_1") (pintype "passive"))
      (node (ref "C155") (pin "1") (pinfunction "1_1") (pintype "passive"))
      (node (ref "C156") (pin "2") (pinfunction "2_2") (pintype "passive"))
      (node (ref "C157") (pin "1") (pinfunction "1_1") (pintype "passive"))
      (node (ref "C158") (pin "1") (pinfunction "1_1") (pintype "passive"))
      (node (ref "C159") (pin "1") (pinfunction "1_1") (pintype "passive"))
      (node (ref "C160") (pin "1") (pinfunction "1_1") (pintype "passive"))
      (node (ref "C161") (pin "1") (pinfunction "1_1") (pintype "passive"))
      (node (ref "C162") (pin "2") (pinfunction "2_2") (pintype "passive"))
      (node (ref "C163") (pin "1") (pinfunction "1_1") (pintype "passive"))
      (node (ref "C164") (pin "1") (pinfunction "1_1") (pintype "passive"))
      (node (ref "C165") (pin "1") (pinfunction "1_1") (pintype "passive"))
      (node (ref "C166") (pin "1") (pinfunction "1_1") (pintype "passive"))
      (node (ref "C167") (pin "1") (pinfunction "1_1") (pintype "passive"))
      (node (ref "C168") (pin "2") (pinfunction "2_2") (pintype "passive"))
      (node (ref "C169") (pin "2") (pinfunction "2_2") (pintype "passive"))
      (node (ref "C170") (pin "2") (pinfunction "2_2") (pintype "passive"))
      (node (ref "C171") (pin "2") (pinfunction "2_2") (pintype "passive"))
      (node (ref "C172") (pin "2") (pinfunction "2_2") (pintype "passive"))
      (node (ref "C173") (pin "2") (pinfunction "2_2") (pintype "passive"))
      (node (ref "C174") (pin "2") (pinfunction "2_2") (pintype "passive"))
      (node (ref "C175") (pin "2") (pinfunction "2_2") (pintype "passive"))
      (node (ref "C176") (pin "2") (pinfunction "2_2") (pintype "passive"))
      (node (ref "C177") (pin "2") (pinfunction "2_2") (pintype "passive"))
      (node (ref "C178") (pin "2") (pinfunction "2_2") (pintype "passive"))
      (node (ref "C179") (pin "2") (pinfunction "2_2") (pintype "passive"))
      (node (ref "C180") (pin "2") (pinfunction "2_2") (pintype "passive"))
      (node (ref "C181") (pin "2") (pinfunction "2_2") (pintype "passive"))
      (node (ref "C182") (pin "2") (pinfunction "2_2") (pintype "passive"))
      (node (ref "C183") (pin "2") (pinfunction "2_2") (pintype "passive"))
      (node (ref "C184") (pin "2") (pinfunction "2_2") (pintype "passive"))
      (node (ref "C185") (pin "2") (pinfunction "2_2") (pintype "passive"))
      (node (ref "C186") (pin "2") (pinfunction "2_2") (pintype "passive"))
      (node (ref "C187") (pin "2") (pinfunction "2_2") (pintype "passive"))
      (node (ref "C188") (pin "2") (pinfunction "2_2") (pintype "passive"))
      (node (ref "C189") (pin "2") (pinfunction "2_2") (pintype "passive"))
      (node (ref "C190") (pin "2") (pinfunction "2_2") (pintype "passive"))
      (node (ref "C191") (pin "2") (pinfunction "2_2") (pintype "passive"))
      (node (ref "C192") (pin "2") (pinfunction "2_2") (pintype "passive"))
      (node (ref "C193") (pin "2") (pinfunction "2_2") (pintype "passive"))
      (node (ref "C194") (pin "2") (pinfunction "2_2") (pintype "passive"))
      (node (ref "C195") (pin "2") (pinfunction "2_2") (pintype "passive"))
      (node (ref "C196") (pin "2") (pinfunction "2_2") (pintype "passive"))
      (node (ref "C197") (pin "2") (pinfunction "2_2") (pintype "passive"))
      (node (ref "C198") (pin "2") (pinfunction "2_2") (pintype "passive"))
      (node (ref "C199") (pin "2") (pinfunction "2_2") (pintype "passive"))
      (node (ref "C200") (pin "2") (pinfunction "2_2") (pintype "passive"))
      (node (ref "C201") (pin "2") (pinfunction "2_2") (pintype "passive"))
      (node (ref "C202") (pin "2") (pinfunction "2_2") (pintype "passive"))
      (node (ref "C203") (pin "2") (pinfunction "2_2") (pintype "passive"))
      (node (ref "C204") (pin "2") (pinfunction "2_2") (pintype "passive"))
      (node (ref "C205") (pin "2") (pinfunction "2_2") (pintype "passive"))
      (node (ref "C206") (pin "2") (pinfunction "2_2") (pintype "passive"))
      (node (ref "C207") (pin "2") (pinfunction "2_2") (pintype "passive"))
      (node (ref "C208") (pin "2") (pinfunction "2_2") (pintype "passive"))
      (node (ref "C209") (pin "2") (pinfunction "2_2") (pintype "passive"))
      (node (ref "C210") (pin "2") (pinfunction "2_2") (pintype "passive"))
      (node (ref "C211") (pin "2") (pinfunction "2_2") (pintype "passive"))
      (node (ref "C212") (pin "2") (pinfunction "2_2") (pintype "passive"))
      (node (ref "C213") (pin "2") (pinfunction "2_2") (pintype "passive"))
      (node (ref "C214") (pin "2") (pinfunction "2_2") (pintype "passive"))
      (node (ref "C215") (pin "2") (pinfunction "2_2") (pintype "passive"))
      (node (ref "C216") (pin "2") (pinfunction "2_2") (pintype "passive"))
      (node (ref "C217") (pin "2") (pinfunction "2_2") (pintype "passive"))
      (node (ref "C218") (pin "2") (pinfunction "2_2") (pintype "passive"))
      (node (ref "C219") (pin "2") (pinfunction "2_2") (pintype "passive"))
      (node (ref "C220") (pin "2") (pinfunction "2_2") (pintype "passive"))
      (node (ref "C221") (pin "2") (pinfunction "2_2") (pintype "passive"))
      (node (ref "C222") (pin "2") (pinfunction "2_2") (pintype "passive"))
      (node (ref "C223") (pin "2") (pinfunction "2_2") (pintype "passive"))
      (node (ref "C224") (pin "2") (pinfunction "2_2") (pintype "passive"))
      (node (ref "C225") (pin "2") (pinfunction "2_2") (pintype "passive"))
      (node (ref "C226") (pin "2") (pinfunction "2_2") (pintype "passive"))
      (node (ref "C227") (pin "2") (pinfunction "2_2") (pintype "passive"))
      (node (ref "C228") (pin "2") (pinfunction "2_2") (pintype "passive"))
      (node (ref "C229") (pin "2") (pinfunction "2_2") (pintype "passive"))
      (node (ref "C230") (pin "2") (pinfunction "2_2") (pintype "passive"))
      (node (ref "C231") (pin "2") (pinfunction "2_2") (pintype "passive"))
      (node (ref "C232") (pin "2") (pinfunction "2_2") (pintype "passive"))
      (node (ref "C233") (pin "2") (pinfunction "2_2") (pintype "passive"))
      (node (ref "C234") (pin "2") (pinfunction "2_2") (pintype "passive"))
      (node (ref "C235") (pin "2") (pinfunction "2_2") (pintype "passive"))
      (node (ref "C236") (pin "2") (pinfunction "2_2") (pintype "passive"))
      (node (ref "C237") (pin "2") (pinfunction "2_2") (pintype "passive"))
      (node (ref "C238") (pin "2") (pinfunction "2_2") (pintype "passive"))
      (node (ref "C239") (pin "2") (pinfunction "2_2") (pintype "passive"))
      (node (ref "C240") (pin "2") (pinfunction "2_2") (pintype "passive"))
      (node (ref "C241") (pin "2") (pinfunction "2_2") (pintype "passive"))
      (node (ref "C242") (pin "2") (pinfunction "2_2") (pintype "passive"))
      (node (ref "C243") (pin "2") (pinfunction "2_2") (pintype "passive"))
      (node (ref "C244") (pin "2") (pinfunction "2_2") (pintype "passive"))
      (node (ref "C245") (pin "2") (pinfunction "2_2") (pintype "passive"))
      (node (ref "C246") (pin "2") (pinfunction "2_2") (pintype "passive"))
      (node (ref "C247") (pin "2") (pinfunction "2_2") (pintype "passive"))
      (node (ref "C248") (pin "2") (pinfunction "2_2") (pintype "passive"))
      (node (ref "C249") (pin "2") (pinfunction "2_2") (pintype "passive"))
      (node (ref "C250") (pin "2") (pinfunction "2_2") (pintype "passive"))
      (node (ref "IC8") (pin "AA1") (pinfunction "GND_AA1") (pintype "passive"))
      (node (ref "IC8") (pin "AA11") (pinfunction "GND_AA11") (pintype "passive"))
      (node (ref "IC8") (pin "AA14") (pinfunction "GND_AA14") (pintype "passive"))
      (node (ref "IC8") (pin "AA17") (pinfunction "GND_AA17") (pintype "passive"))
      (node (ref "IC8") (pin "AA2") (pinfunction "GND_AA2") (pintype "passive"))
      (node (ref "IC8") (pin "AA5") (pinfunction "GND_AA5") (pintype "passive"))
      (node (ref "IC8") (pin "AA8") (pinfunction "GND_AA8") (pintype "passive"))
      (node (ref "IC8") (pin "AB2") (pinfunction "GND_AB2") (pintype "passive"))
      (node (ref "IC8") (pin "B11") (pinfunction "GND_B11") (pintype "passive"))
      (node (ref "IC8") (pin "B14") (pinfunction "GND_B14") (pintype "passive"))
      (node (ref "IC8") (pin "B17") (pinfunction "GND_B17") (pintype "passive"))
      (node (ref "IC8") (pin "B2") (pinfunction "GND_B2") (pintype "passive"))
      (node (ref "IC8") (pin "B5") (pinfunction "GND_B5") (pintype "passive"))
      (node (ref "IC8") (pin "B8") (pinfunction "GND_B8") (pintype "passive"))
      (node (ref "IC8") (pin "C21") (pinfunction "GND_C21") (pintype "passive"))
      (node (ref "IC8") (pin "D18") (pinfunction "GND_D18") (pintype "passive"))
      (node (ref "IC8") (pin "E1") (pinfunction "GND_E1") (pintype "passive"))
      (node (ref "IC8") (pin "E19") (pinfunction "GND_E19") (pintype "passive"))
      (node (ref "IC8") (pin "E2") (pinfunction "GND_E2") (pintype "passive"))
      (node (ref "IC8") (pin "E7") (pinfunction "GND_E7") (pintype "passive"))
      (node (ref "IC8") (pin "F11") (pinfunction "GND_F11") (pintype "passive"))
      (node (ref "IC8") (pin "F13") (pinfunction "GND_F13") (pintype "passive"))
      (node (ref "IC8") (pin "F15") (pinfunction "GND_F15") (pintype "passive"))
      (node (ref "IC8") (pin "F21") (pinfunction "GND_F21") (pintype "passive"))
      (node (ref "IC8") (pin "F3") (pinfunction "GND_F3") (pintype "passive"))
      (node (ref "IC8") (pin "F9") (pinfunction "GND_F9") (pintype "passive"))
      (node (ref "IC8") (pin "G1") (pinfunction "GND_G1") (pintype "passive"))
      (node (ref "IC8") (pin "G2") (pinfunction "GND_G2") (pintype "passive"))
      (node (ref "IC8") (pin "H11") (pinfunction "GND_H11") (pintype "passive"))
      (node (ref "IC8") (pin "H18") (pinfunction "GND_H18") (pintype "passive"))
      (node (ref "IC8") (pin "H5") (pinfunction "GND_H5") (pintype "passive"))
      (node (ref "IC8") (pin "J1") (pinfunction "GND_J1") (pintype "passive"))
      (node (ref "IC8") (pin "J2") (pinfunction "GND_J2") (pintype "passive"))
      (node (ref "IC8") (pin "J6") (pinfunction "GND_J6") (pintype "passive"))
      (node (ref "IC8") (pin "J8") (pinfunction "GND_J8") (pintype "passive"))
      (node (ref "IC8") (pin "K11") (pinfunction "GND_K11") (pintype "passive"))
      (node (ref "IC8") (pin "K15") (pinfunction "GND_K15") (pintype "passive"))
      (node (ref "IC8") (pin "K21") (pinfunction "GND_K21") (pintype "passive"))
      (node (ref "IC8") (pin "K5") (pinfunction "GND_K5") (pintype "passive"))
      (node (ref "IC8") (pin "K7") (pinfunction "GND_K7") (pintype "passive"))
      (node (ref "IC8") (pin "K9") (pinfunction "GND_K9") (pintype "passive"))
      (node (ref "IC8") (pin "L1") (pinfunction "GND_L1") (pintype "passive"))
      (node (ref "IC8") (pin "L10") (pinfunction "GND_L10") (pintype "passive"))
      (node (ref "IC8") (pin "L12") (pinfunction "GND_L12") (pintype "passive"))
      (node (ref "IC8") (pin "L18") (pinfunction "GND_L18") (pintype "passive"))
      (node (ref "IC8") (pin "L2") (pinfunction "GND_L2") (pintype "passive"))
      (node (ref "IC8") (pin "L6") (pinfunction "GND_L6") (pintype "passive"))
      (node (ref "IC8") (pin "L8") (pinfunction "GND_L8") (pintype "passive"))
      (node (ref "IC8") (pin "M3") (pinfunction "GND_M3") (pintype "passive"))
      (node (ref "IC8") (pin "M5") (pinfunction "GND_M5") (pintype "passive"))
      (node (ref "IC8") (pin "M9") (pinfunction "GND_M9") (pintype "passive"))
      (node (ref "IC8") (pin "N1") (pinfunction "GND_N1") (pintype "passive"))
      (node (ref "IC8") (pin "N10") (pinfunction "GND_N10") (pintype "passive"))
      (node (ref "IC8") (pin "N2") (pinfunction "GND_N2") (pintype "passive"))
      (node (ref "IC8") (pin "N4") (pinfunction "GND_N4") (pintype "passive"))
      (node (ref "IC8") (pin "N6") (pinfunction "GND_N6") (pintype "passive"))
      (node (ref "IC8") (pin "P11") (pinfunction "GND_P11") (pintype "passive"))
      (node (ref "IC8") (pin "P16") (pinfunction "GND_P16") (pintype "passive"))
      (node (ref "IC8") (pin "P18") (pinfunction "GND_P18") (pintype "passive"))
      (node (ref "IC8") (pin "P21") (pinfunction "GND_P21") (pintype "passive"))
      (node (ref "IC8") (pin "P9") (pinfunction "GND_P9") (pintype "passive"))
      (node (ref "IC8") (pin "R1") (pinfunction "GND_R1") (pintype "passive"))
      (node (ref "IC8") (pin "R12") (pinfunction "GND_R12") (pintype "passive"))
      (node (ref "IC8") (pin "R2") (pinfunction "GND_R2") (pintype "passive"))
      (node (ref "IC8") (pin "R6") (pinfunction "GND_R6") (pintype "passive"))
      (node (ref "IC8") (pin "T4") (pinfunction "GND_T4") (pintype "passive"))
      (node (ref "IC8") (pin "U1") (pinfunction "GND_U1") (pintype "passive"))
      (node (ref "IC8") (pin "U10") (pinfunction "GND_U10") (pintype "passive"))
      (node (ref "IC8") (pin "U17") (pinfunction "GND_U17") (pintype "passive"))
      (node (ref "IC8") (pin "U2") (pinfunction "GND_U2") (pintype "passive"))
      (node (ref "IC8") (pin "U21") (pinfunction "GND_U21") (pintype "passive"))
      (node (ref "IC8") (pin "U3") (pinfunction "GND_U3") (pintype "passive"))
      (node (ref "IC8") (pin "V11") (pinfunction "GND_V11") (pintype "passive"))
      (node (ref "IC8") (pin "V14") (pinfunction "GND_V14") (pintype "passive"))
      (node (ref "IC8") (pin "V19") (pinfunction "GND_V19") (pintype "passive"))
      (node (ref "IC8") (pin "V5") (pinfunction "GND_V5") (pintype "passive"))
      (node (ref "IC8") (pin "V8") (pinfunction "GND_V8") (pintype "passive"))
      (node (ref "IC8") (pin "W1") (pinfunction "GND_W1") (pintype "passive"))
      (node (ref "IC8") (pin "W2") (pinfunction "GND_W2") (pintype "passive"))
      (node (ref "IC8") (pin "Y21") (pinfunction "GND_Y21") (pintype "passive"))
      (node (ref "R71") (pin "2") (pinfunction "2_2") (pintype "passive"))
    )
    (net (code "2") (name "Net-(IC8J-RREF0)") (class "Default")
      (node (ref "IC8") (pin "AB1") (pinfunction "RREF0_AB1") (pintype "bidirectional"))
      (node (ref "R71") (pin "1") (pinfunction "1_1") (pintype "passive"))
    )
    (net (code "3") (name "VCC1P2") (class "Default")
      (node (ref "C120") (pin "2") (pinfunction "2_2") (pintype "passive"))
      (node (ref "C121") (pin "2") (pinfunction "2_2") (pintype "passive"))
      (node (ref "C122") (pin "2") (pinfunction "2_2") (pintype "passive"))
      (node (ref "C123") (pin "2") (pinfunction "2_2") (pintype "passive"))
      (node (ref "C124") (pin "2") (pinfunction "2_2") (pintype "passive"))
      (node (ref "C125") (pin "1") (pinfunction "1_1") (pintype "passive"))
      (node (ref "C126") (pin "1") (pinfunction "1_1") (pintype "passive"))
      (node (ref "C213") (pin "1") (pinfunction "1_1") (pintype "passive"))
      (node (ref "C214") (pin "1") (pinfunction "1_1") (pintype "passive"))
      (node (ref "C215") (pin "1") (pinfunction "1_1") (pintype "passive"))
      (node (ref "C216") (pin "1") (pinfunction "1_1") (pintype "passive"))
      (node (ref "C217") (pin "1") (pinfunction "1_1") (pintype "passive"))
      (node (ref "C218") (pin "1") (pinfunction "1_1") (pintype "passive"))
      (node (ref "C219") (pin "1") (pinfunction "1_1") (pintype "passive"))
      (node (ref "C220") (pin "1") (pinfunction "1_1") (pintype "passive"))
      (node (ref "C221") (pin "1") (pinfunction "1_1") (pintype "passive"))
      (node (ref "C222") (pin "1") (pinfunction "1_1") (pintype "passive"))
      (node (ref "C223") (pin "1") (pinfunction "1_1") (pintype "passive"))
      (node (ref "C224") (pin "1") (pinfunction "1_1") (pintype "passive"))
      (node (ref "C225") (pin "1") (pinfunction "1_1") (pintype "passive"))
      (node (ref "C226") (pin "1") (pinfunction "1_1") (pintype "passive"))
      (node (ref "C227") (pin "1") (pinfunction "1_1") (pintype "passive"))
      (node (ref "C235") (pin "1") (pinfunction "1_1") (pintype "passive"))
      (node (ref "C236") (pin "1") (pinfunction "1_1") (pintype "passive"))
      (node (ref "C237") (pin "1") (pinfunction "1_1") (pintype "passive"))
      (node (ref "C238") (pin "1") (pinfunction "1_1") (pintype "passive"))
      (node (ref "C239") (pin "1") (pinfunction "1_1") (pintype "passive"))
      (node (ref "C240") (pin "1") (pinfunction "1_1") (pintype "passive"))
      (node (ref "C241") (pin "1") (pinfunction "1_1") (pintype "passive"))
      (node (ref "C242") (pin "1") (pinfunction "1_1") (pintype "passive"))
      (node (ref "C243") (pin "1") (pinfunction "1_1") (pintype "passive"))
      (node (ref "C244") (pin "1") (pinfunction "1_1") (pintype "passive"))
      (node (ref "C245") (pin "1") (pinfunction "1_1") (pintype "passive"))
      (node (ref "C246") (pin "1") (pinfunction "1_1") (pintype "passive"))
      (node (ref "C247") (pin "1") (pinfunction "1_1") (pintype "passive"))
      (node (ref "C248") (pin "1") (pinfunction "1_1") (pintype "passive"))
      (node (ref "C249") (pin "1") (pinfunction "1_1") (pintype "passive"))
      (node (ref "C250") (pin "1") (pinfunction "1_1") (pintype "passive"))
      (node (ref "FR36") (pin "1") (pinfunction "1_1") (pintype "passive"))
      (node (ref "FR37") (pin "1") (pinfunction "1_1") (pintype "passive"))
      (node (ref "IC8") (pin "F7") (pinfunction "VCCINT_F7") (pintype "bidirectional"))
      (node (ref "IC8") (pin "G13") (pinfunction "VCCINT_G13") (pintype "bidirectional"))
      (node (ref "IC8") (pin "G9") (pinfunction "VCCINT_G9") (pintype "bidirectional"))
      (node (ref "IC8") (pin "H6") (pinfunction "VCCINT_H6") (pintype "bidirectional"))
      (node (ref "IC8") (pin "J11") (pinfunction "VCCINT_J11") (pintype "bidirectional"))
      (node (ref "IC8") (pin "J17") (pinfunction "VCCINT_J17") (pintype "bidirectional"))
      (node (ref "IC8") (pin "J5") (pinfunction "VCCINT_J5") (pintype "bidirectional"))
      (node (ref "IC8") (pin "J7") (pinfunction "VCCINT_J7") (pintype "bidirectional"))
      (node (ref "IC8") (pin "J9") (pinfunction "VCCINT_J9") (pintype "bidirectional"))
      (node (ref "IC8") (pin "K16") (pinfunction "VCCINT_K16") (pintype "bidirectional"))
      (node (ref "IC8") (pin "K6") (pinfunction "VCCINT_K6") (pintype "bidirectional"))
      (node (ref "IC8") (pin "K8") (pinfunction "VCCINT_K8") (pintype "bidirectional"))
      (node (ref "IC8") (pin "L11") (pinfunction "VCCINT_L11") (pintype "bidirectional"))
      (node (ref "IC8") (pin "L17") (pinfunction "VCCINT_L17") (pintype "bidirectional"))
      (node (ref "IC8") (pin "L5") (pinfunction "VCCINT_L5") (pintype "bidirectional"))
      (node (ref "IC8") (pin "L7") (pinfunction "VCCINT_L7") (pintype "bidirectional"))
      (node (ref "IC8") (pin "L9") (pinfunction "VCCINT_L9") (pintype "bidirectional"))
      (node (ref "IC8") (pin "M10") (pinfunction "VCCINT_M10") (pintype "bidirectional"))
      (node (ref "IC8") (pin "M12") (pinfunction "VCCINT_M12") (pintype "bidirectional"))
      (node (ref "IC8") (pin "M6") (pinfunction "VCCINT_M6") (pintype "bidirectional"))
      (node (ref "IC8") (pin "N16") (pinfunction "VCCINT_N16") (pintype "bidirectional"))
      (node (ref "IC8") (pin "N5") (pinfunction "VCCINT_N5") (pintype "bidirectional"))
      (node (ref "IC8") (pin "N9") (pinfunction "VCCINT_N9") (pintype "bidirectional"))
      (node (ref "IC8") (pin "P12") (pinfunction "VCCINT_P12") (pintype "bidirectional"))
      (node (ref "IC8") (pin "P17") (pinfunction "VCCINT_P17") (pintype "bidirectional"))
      (node (ref "IC8") (pin "P6") (pinfunction "VCCINT_P6") (pintype "bidirectional"))
      (node (ref "IC8") (pin "P8") (pinfunction "VCCINT_P8") (pintype "bidirectional"))
      (node (ref "IC8") (pin "R7") (pinfunction "VCCINT_R7") (pintype "bidirectional"))
      (node (ref "IC8") (pin "T10") (pinfunction "VCCINT_T10") (pintype "bidirectional"))
      (node (ref "IC8") (pin "T12") (pinfunction "VCCINT_T12") (pintype "bidirectional"))
      (node (ref "IC8") (pin "U16") (pinfunction "VCCINT_U16") (pintype "bidirectional"))
    )
    (net (code "4") (name "VCC1P2D_FPGA") (class "Default")
      (node (ref "C127") (pin "2") (pinfunction "2_2") (pintype "passive"))
      (node (ref "C128") (pin "2") (pinfunction "2_2") (pintype "passive"))
      (node (ref "C129") (pin "2") (pinfunction "2_2") (pintype "passive"))
      (node (ref "C130") (pin "2") (pinfunction "2_2") (pintype "passive"))
      (node (ref "C131") (pin "1") (pinfunction "1_1") (pintype "passive"))
      (node (ref "C132") (pin "1") (pinfunction "1_1") (pintype "passive"))
      (node (ref "C207") (pin "1") (pinfunction "1_1") (pintype "passive"))
      (node (ref "C208") (pin "1") (pinfunction "1_1") (pintype "passive"))
      (node (ref "C209") (pin "1") (pinfunction "1_1") (pintype "passive"))
      (node (ref "C210") (pin "1") (pinfunction "1_1") (pintype "passive"))
      (node (ref "C211") (pin "1") (pinfunction "1_1") (pintype "passive"))
      (node (ref "C212") (pin "1") (pinfunction "1_1") (pintype "passive"))
      (node (ref "FR36") (pin "2") (pinfunction "2_2") (pintype "passive"))
      (node (ref "IC8") (pin "E18") (pinfunction "VCCD_PLL_E18") (pintype "bidirectional"))
      (node (ref "IC8") (pin "G3") (pinfunction "VCCD_PLL_G3") (pintype "bidirectional"))
      (node (ref "IC8") (pin "M4") (pinfunction "VCCD_PLL_M4") (pintype "bidirectional"))
      (node (ref "IC8") (pin "R4") (pinfunction "VCCD_PLL_R4") (pintype "bidirectional"))
      (node (ref "IC8") (pin "U4") (pinfunction "VCCD_PLL_U4") (pintype "bidirectional"))
      (node (ref "IC8") (pin "V18") (pinfunction "VCCD_PLL_V18") (pintype "bidirectional"))
    )
    (net (code "5") (name "VCC1P2L_FPGA") (class "Default")
      (node (ref "C133") (pin "2") (pinfunction "2_2") (pintype "passive"))
      (node (ref "C134") (pin "2") (pinfunction "2_2") (pintype "passive"))
      (node (ref "C135") (pin "2") (pinfunction "2_2") (pintype "passive"))
      (node (ref "C136") (pin "2") (pinfunction "2_2") (pintype "passive"))
      (node (ref "C137") (pin "2") (pinfunction "2_2") (pintype "passive"))
      (node (ref "C138") (pin "1") (pinfunction "1_1") (pintype "passive"))
      (node (ref "C169") (pin "1") (pinfunction "1_1") (pintype "passive"))
      (node (ref "C170") (pin "1") (pinfunction "1_1") (pintype "passive"))
      (node (ref "C171") (pin "1") (pinfunction "1_1") (pintype "passive"))
      (node (ref "C172") (pin "1") (pinfunction "1_1") (pintype "passive"))
      (node (ref "C173") (pin "1") (pinfunction "1_1") (pintype "passive"))
      (node (ref "FR37") (pin "2") (pinfunction "2_2") (pintype "passive"))
      (node (ref "IC8") (pin "K3") (pinfunction "VCCL_GXB_K3") (pintype "bidirectional"))
      (node (ref "IC8") (pin "L3") (pinfunction "VCCL_GXB_L3") (pintype "bidirectional"))
      (node (ref "IC8") (pin "N3") (pinfunction "VCCL_GXB_N3") (pintype "bidirectional"))
      (node (ref "IC8") (pin "T3") (pinfunction "VCCL_GXB_T3") (pintype "bidirectional"))
      (node (ref "IC8") (pin "V3") (pinfunction "VCCL_GXB_V3") (pintype "bidirectional"))
    )
    (net (code "6") (name "VCC1P8") (class "Default")
      (node (ref "C139") (pin "2") (pinfunction "2_2") (pintype "passive"))
      (node (ref "C140") (pin "2") (pinfunction "2_2") (pintype "passive"))
      (node (ref "C141") (pin "2") (pinfunction "2_2") (pintype "passive"))
      (node (ref "C142") (pin "2") (pinfunction "2_2") (pintype "passive"))
      (node (ref "C143") (pin "2") (pinfunction "2_2") (pintype "passive"))
      (node (ref "C144") (pin "1") (pinfunction "1_1") (pintype "passive"))
      (node (ref "C195") (pin "1") (pinfunction "1_1") (pintype "passive"))
      (node (ref "C196") (pin "1") (pinfunction "1_1") (pintype "passive"))
      (node (ref "C197") (pin "1") (pinfunction "1_1") (pintype "passive"))
      (node (ref "C198") (pin "1") (pinfunction "1_1") (pintype "passive"))
      (node (ref "C199") (pin "1") (pinfunction "1_1") (pintype "passive"))
      (node (ref "C200") (pin "1") (pinfunction "1_1") (pintype "passive"))
      (node (ref "C201") (pin "1") (pinfunction "1_1") (pintype "passive"))
      (node (ref "C202") (pin "1") (pinfunction "1_1") (pintype "passive"))
      (node (ref "C203") (pin "1") (pinfunction "1_1") (pintype "passive"))
      (node (ref "C204") (pin "1") (pinfunction "1_1") (pintype "passive"))
      (node (ref "C205") (pin "1") (pinfunction "1_1") (pintype "passive"))
      (node (ref "C206") (pin "1") (pinfunction "1_1") (pintype "passive"))
      (node (ref "IC8") (pin "N18") (pinfunction "VCCIO5_N18") (pintype "bidirectional"))
      (node (ref "IC8") (pin "P19") (pinfunction "VCCIO5_P19") (pintype "bidirectional"))
      (node (ref "IC8") (pin "R18") (pinfunction "VCCIO5_R18") (pintype "bidirectional"))
      (node (ref "IC8") (pin "U11") (pinfunction "VCCIO3_U11") (pintype "bidirectional"))
      (node (ref "IC8") (pin "U13") (pinfunction "VCCIO4_U13") (pintype "bidirectional"))
      (node (ref "IC8") (pin "U8") (pinfunction "VCCIO3_U8") (pintype "bidirectional"))
      (node (ref "IC8") (pin "U9") (pinfunction "VCCIO3_U9") (pintype "bidirectional"))
      (node (ref "IC8") (pin "V10") (pinfunction "VCCIO3_V10") (pintype "bidirectional"))
      (node (ref "IC8") (pin "V12") (pinfunction "VCCIO3_V12") (pintype "bidirectional"))
      (node (ref "IC8") (pin "V15") (pinfunction "VCCIO4_V15") (pintype "bidirectional"))
      (node (ref "IC8") (pin "V16") (pinfunction "VCCIO4_V16") (pintype "bidirectional"))
      (node (ref "IC8") (pin "V17") (pinfunction "VCCIO4_V17") (pintype "bidirectional"))
    )
    (net (code "7") (name "VCC2P5") (class "Default")
      (node (ref "FR38") (pin "1") (pinfunction "1_1") (pintype "passive"))
      (node (ref "FR39") (pin "1") (pinfunction "1_1") (pintype "passive"))
    )
    (net (code "8") (name "VCC2P5AH_FPGA") (class "Default")
      (node (ref "C151") (pin "2") (pinfunction "2_2") (pintype "passive"))
      (node (ref "C152") (pin "2") (pinfunction "2_2") (pintype "passive"))
      (node (ref "C153") (pin "2") (pinfunction "2_2") (pintype "passive"))
      (node (ref "C154") (pin "2") (pinfunction "2_2") (pintype "passive"))
      (node (ref "C155") (pin "2") (pinfunction "2_2") (pintype "passive"))
      (node (ref "C156") (pin "1") (pinfunction "1_1") (pintype "passive"))
      (node (ref "C183") (pin "1") (pinfunction "1_1") (pintype "passive"))
      (node (ref "C184") (pin "1") (pinfunction "1_1") (pintype "passive"))
      (node (ref "C185") (pin "1") (pinfunction "1_1") (pintype "passive"))
      (node (ref "C186") (pin "1") (pinfunction "1_1") (pintype "passive"))
      (node (ref "C187") (pin "1") (pinfunction "1_1") (pintype "passive"))
      (node (ref "FR39") (pin "2") (pinfunction "2_2") (pintype "passive"))
      (node (ref "IC8") (pin "H3") (pinfunction "VCCH_GXB_H3") (pintype "bidirectional"))
      (node (ref "IC8") (pin "J3") (pinfunction "VCCA_GXB_J3") (pintype "bidirectional"))
      (node (ref "IC8") (pin "P3") (pinfunction "VCCH_GXB_P3") (pintype "bidirectional"))
      (node (ref "IC8") (pin "R3") (pinfunction "VCCA_GXB_R3") (pintype "bidirectional"))
      (node (ref "IC8") (pin "W3") (pinfunction "VCCA_GXB_W3") (pintype "bidirectional"))
    )
    (net (code "9") (name "VCC2P5A_FPGA") (class "Default")
      (node (ref "C145") (pin "2") (pinfunction "2_2") (pintype "passive"))
      (node (ref "C146") (pin "2") (pinfunction "2_2") (pintype "passive"))
      (node (ref "C147") (pin "2") (pinfunction "2_2") (pintype "passive"))
      (node (ref "C148") (pin "2") (pinfunction "2_2") (pintype "passive"))
      (node (ref "C149") (pin "2") (pinfunction "2_2") (pintype "passive"))
      (node (ref "C150") (pin "1") (pinfunction "1_1") (pintype "passive"))
      (node (ref "C188") (pin "1") (pinfunction "1_1") (pintype "passive"))
      (node (ref "C189") (pin "1") (pinfunction "1_1") (pintype "passive"))
      (node (ref "C190") (pin "1") (pinfunction "1_1") (pintype "passive"))
      (node (ref "C191") (pin "1") (pinfunction "1_1") (pintype "passive"))
      (node (ref "C192") (pin "1") (pinfunction "1_1") (pintype "passive"))
      (node (ref "C193") (pin "1") (pinfunction "1_1") (pintype "passive"))
      (node (ref "C194") (pin "1") (pinfunction "1_1") (pintype "passive"))
      (node (ref "FR38") (pin "2") (pinfunction "2_2") (pintype "passive"))
      (node (ref "IC8") (pin "F19") (pinfunction "VCCA_F19") (pintype "bidirectional"))
      (node (ref "IC8") (pin "F4") (pinfunction "VCCA_F4") (pintype "bidirectional"))
      (node (ref "IC8") (pin "L4") (pinfunction "VCCA_L4") (pintype "bidirectional"))
      (node (ref "IC8") (pin "P7") (pinfunction "VCC_CLKIN3B_P7") (pintype "bidirectional"))
      (node (ref "IC8") (pin "T5") (pinfunction "VCCA_T5") (pintype "bidirectional"))
      (node (ref "IC8") (pin "U19") (pinfunction "VCCA_U19") (pintype "bidirectional"))
      (node (ref "IC8") (pin "V4") (pinfunction "VCCA_V4") (pintype "bidirectional"))
    )
    (net (code "10") (name "VCC3P3") (class "Default")
      (node (ref "C163") (pin "2") (pinfunction "2_2") (pintype "passive"))
      (node (ref "C164") (pin "2") (pinfunction "2_2") (pintype "passive"))
      (node (ref "C165") (pin "2") (pinfunction "2_2") (pintype "passive"))
      (node (ref "C166") (pin "2") (pinfunction "2_2") (pintype "passive"))
      (node (ref "C167") (pin "2") (pinfunction "2_2") (pintype "passive"))
      (node (ref "C168") (pin "1") (pinfunction "1_1") (pintype "passive"))
      (node (ref "C174") (pin "1") (pinfunction "1_1") (pintype "passive"))
      (node (ref "C175") (pin "1") (pinfunction "1_1") (pintype "passive"))
      (node (ref "C176") (pin "1") (pinfunction "1_1") (pintype "passive"))
      (node (ref "C177") (pin "1") (pinfunction "1_1") (pintype "passive"))
      (node (ref "C178") (pin "1") (pinfunction "1_1") (pintype "passive"))
      (node (ref "C179") (pin "1") (pinfunction "1_1") (pintype "passive"))
      (node (ref "C180") (pin "1") (pinfunction "1_1") (pintype "passive"))
      (node (ref "C181") (pin "1") (pinfunction "1_1") (pintype "passive"))
      (node (ref "C182") (pin "1") (pinfunction "1_1") (pintype "passive"))
      (node (ref "IC8") (pin "E13") (pinfunction "VCCIO7_E13") (pintype "bidirectional"))
      (node (ref "IC8") (pin "E14") (pinfunction "VCCIO7_E14") (pintype "bidirectional"))
      (node (ref "IC8") (pin "E15") (pinfunction "VCCIO7_E15") (pintype "bidirectional"))
      (node (ref "IC8") (pin "E16") (pinfunction "VCCIO7_E16") (pintype "bidirectional"))
      (node (ref "IC8") (pin "F14") (pinfunction "VCCIO7_F14") (pintype "bidirectional"))
      (node (ref "IC8") (pin "G4") (pinfunction "VCCIO9_G4") (pintype "bidirectional"))
      (node (ref "IC8") (pin "H19") (pinfunction "VCCIO6_H19") (pintype "bidirectional"))
      (node (ref "IC8") (pin "J18") (pinfunction "VCCIO6_J18") (pintype "bidirectional"))
      (node (ref "IC8") (pin "K18") (pinfunction "VCCIO6_K18") (pintype "bidirectional"))
    )
    (net (code "11") (name "VDIO_LMS_FPGA") (class "Default")
      (node (ref "C157") (pin "2") (pinfunction "2_2") (pintype "passive"))
      (node (ref "C158") (pin "2") (pinfunction "2_2") (pintype "passive"))
      (node (ref "C159") (pin "2") (pinfunction "2_2") (pintype "passive"))
      (node (ref "C160") (pin "2") (pinfunction "2_2") (pintype "passive"))
      (node (ref "C161") (pin "2") (pinfunction "2_2") (pintype "passive"))
      (node (ref "C162") (pin "1") (pinfunction "1_1") (pintype "passive"))
      (node (ref "C228") (pin "1") (pinfunction "1_1") (pintype "passive"))
      (node (ref "C229") (pin "1") (pinfunction "1_1") (pintype "passive"))
      (node (ref "C230") (pin "1") (pinfunction "1_1") (pintype "passive"))
      (node (ref "C231") (pin "1") (pinfunction "1_1") (pintype "passive"))
      (node (ref "C232") (pin "1") (pinfunction "1_1") (pintype "passive"))
      (node (ref "C233") (pin "1") (pinfunction "1_1") (pintype "passive"))
      (node (ref "C234") (pin "1") (pinfunction "1_1") (pintype "passive"))
      (node (ref "IC8") (pin "E10") (pinfunction "VCCIO8_E10") (pintype "bidirectional"))
      (node (ref "IC8") (pin "E11") (pinfunction "VCCIO8_E11") (pintype "bidirectional"))
      (node (ref "IC8") (pin "E12") (pinfunction "VCCIO8_E12") (pintype "bidirectional"))
      (node (ref "IC8") (pin "E9") (pinfunction "VCCIO8_E9") (pintype "bidirectional"))
      (node (ref "IC8") (pin "F10") (pinfunction "VCCIO8_F10") (pintype "bidirectional"))
      (node (ref "IC8") (pin "H10") (pinfunction "VCC_CLKIN8A_H10") (pintype "bidirectional"))
      (node (ref "IC8") (pin "N12") (pinfunction "VCC_CLKIN3A_N12") (pintype "bidirectional"))
    )
    (net (code "12") (name "unconnected-(IC8J-NC-PadAA3)") (class "Default")
      (node (ref "IC8") (pin "AA3") (pinfunction "NC_AA3") (pintype "bidirectional+no_connect"))
    )
    (net (code "13") (name "unconnected-(IC8J-NC-PadY3)") (class "Default")
      (node (ref "IC8") (pin "Y3") (pinfunction "NC_Y3") (pintype "bidirectional+no_connect"))
    )
  )
)
